# CANnode.net
KiCad netlist of a schematic drawn in EAGLE
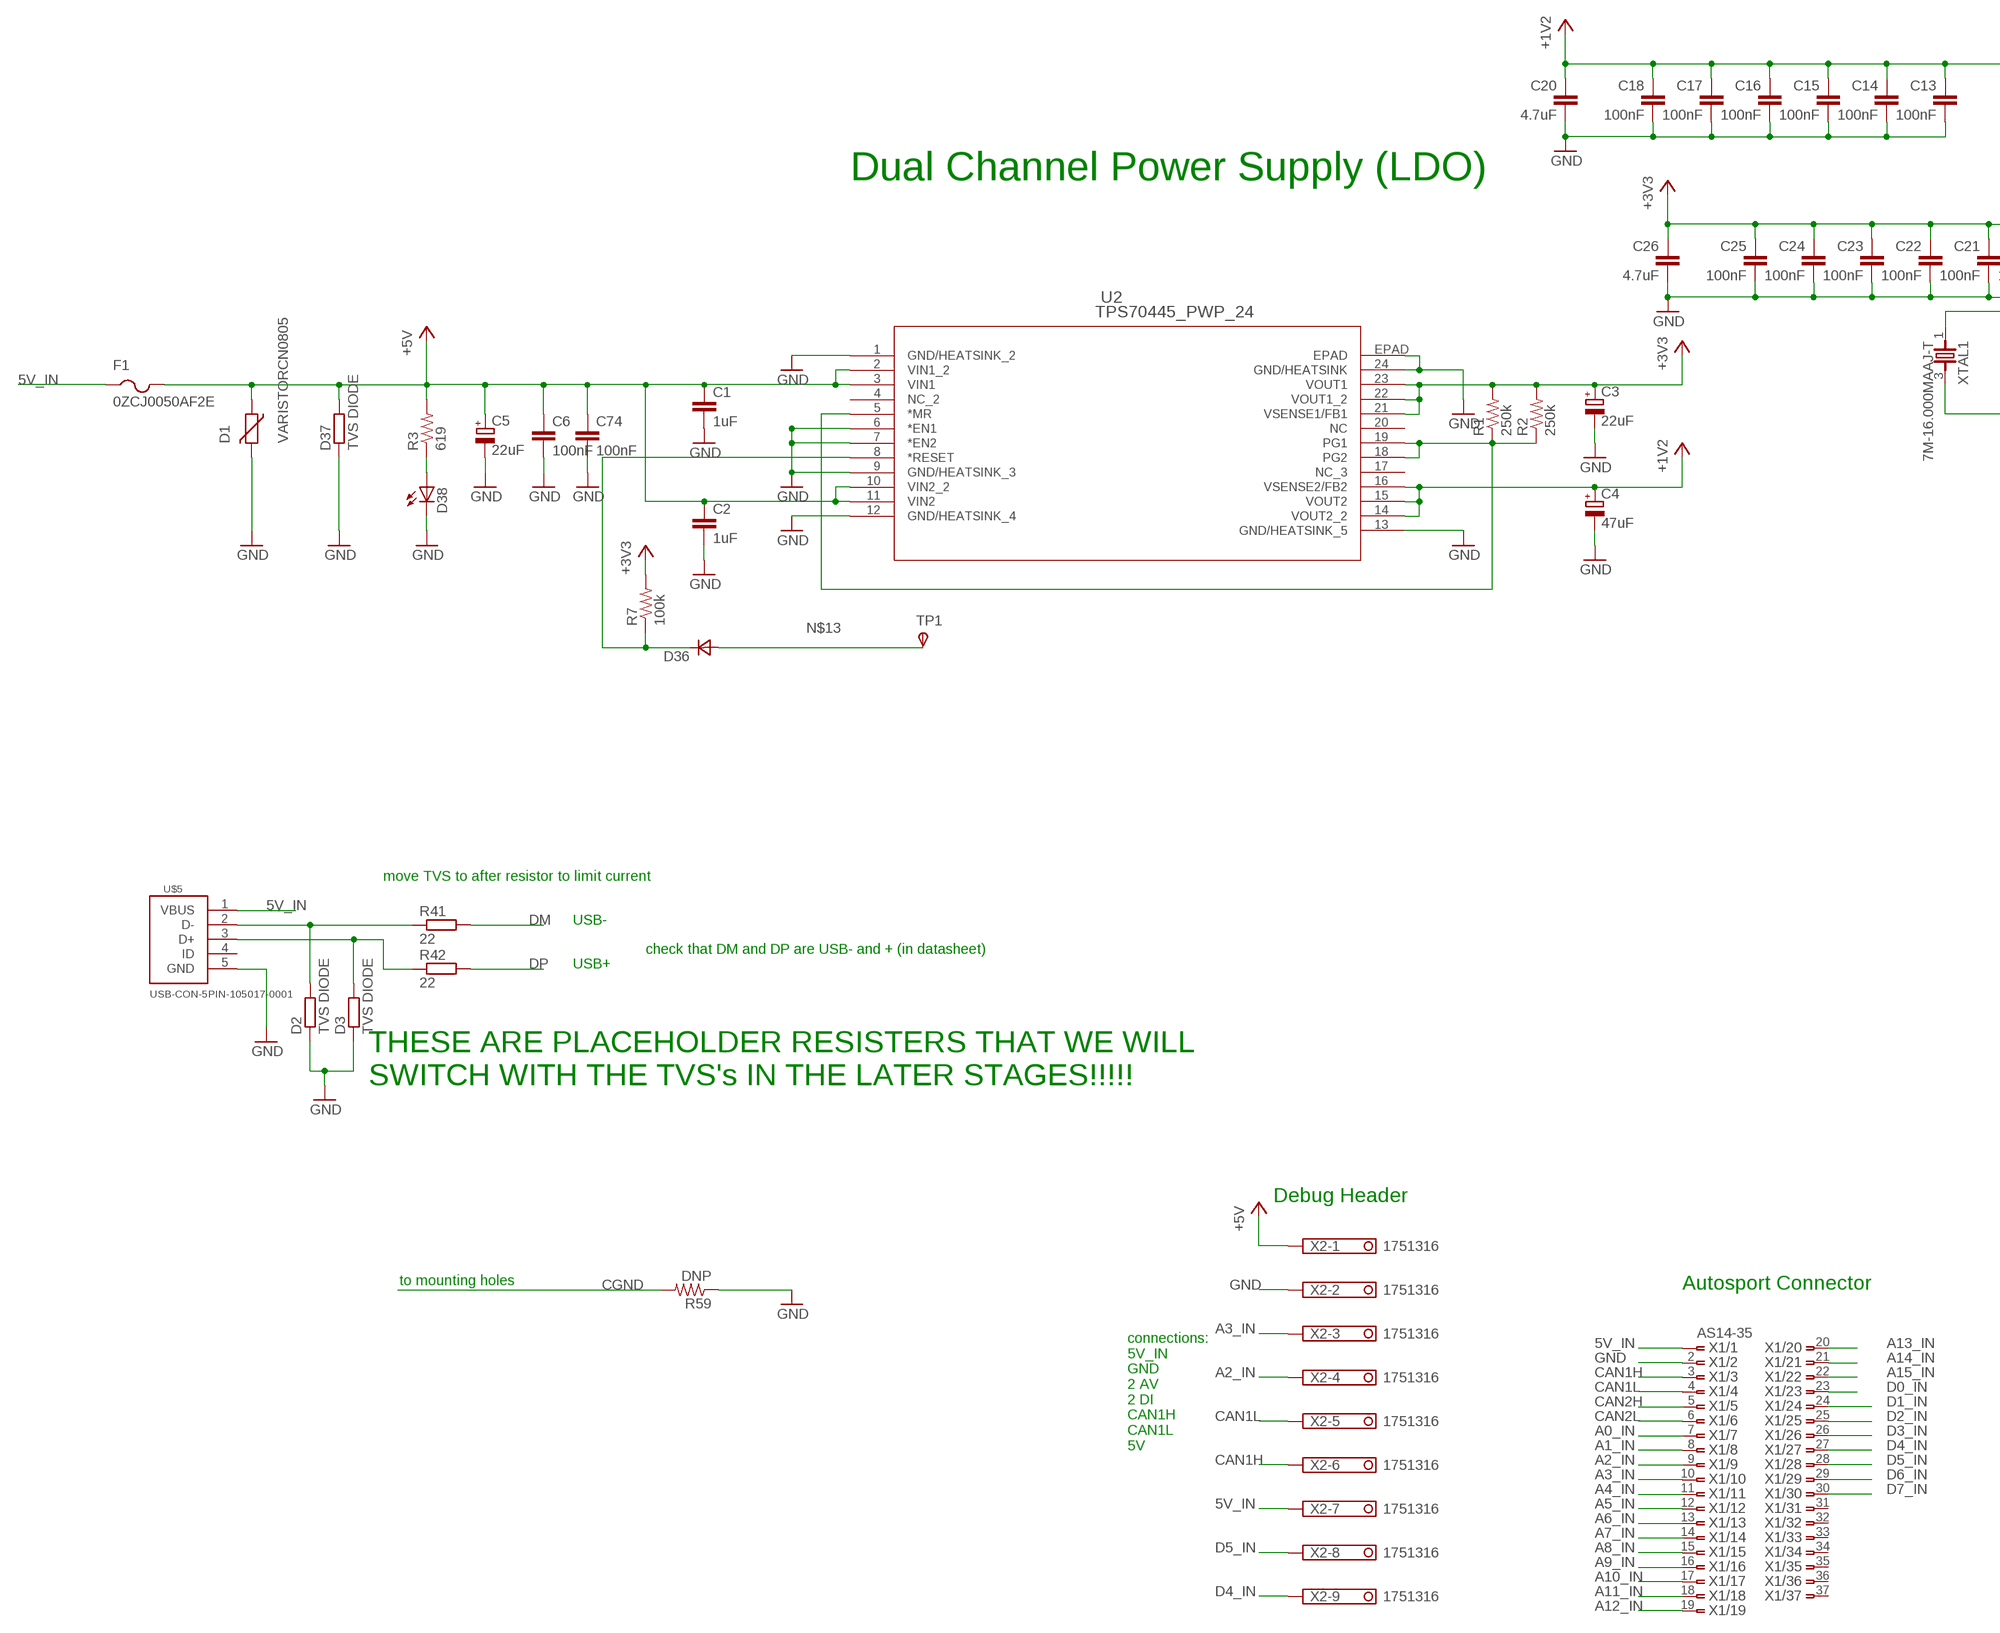
[diagram p0: schematic, sheet 1, part 1 of 3]
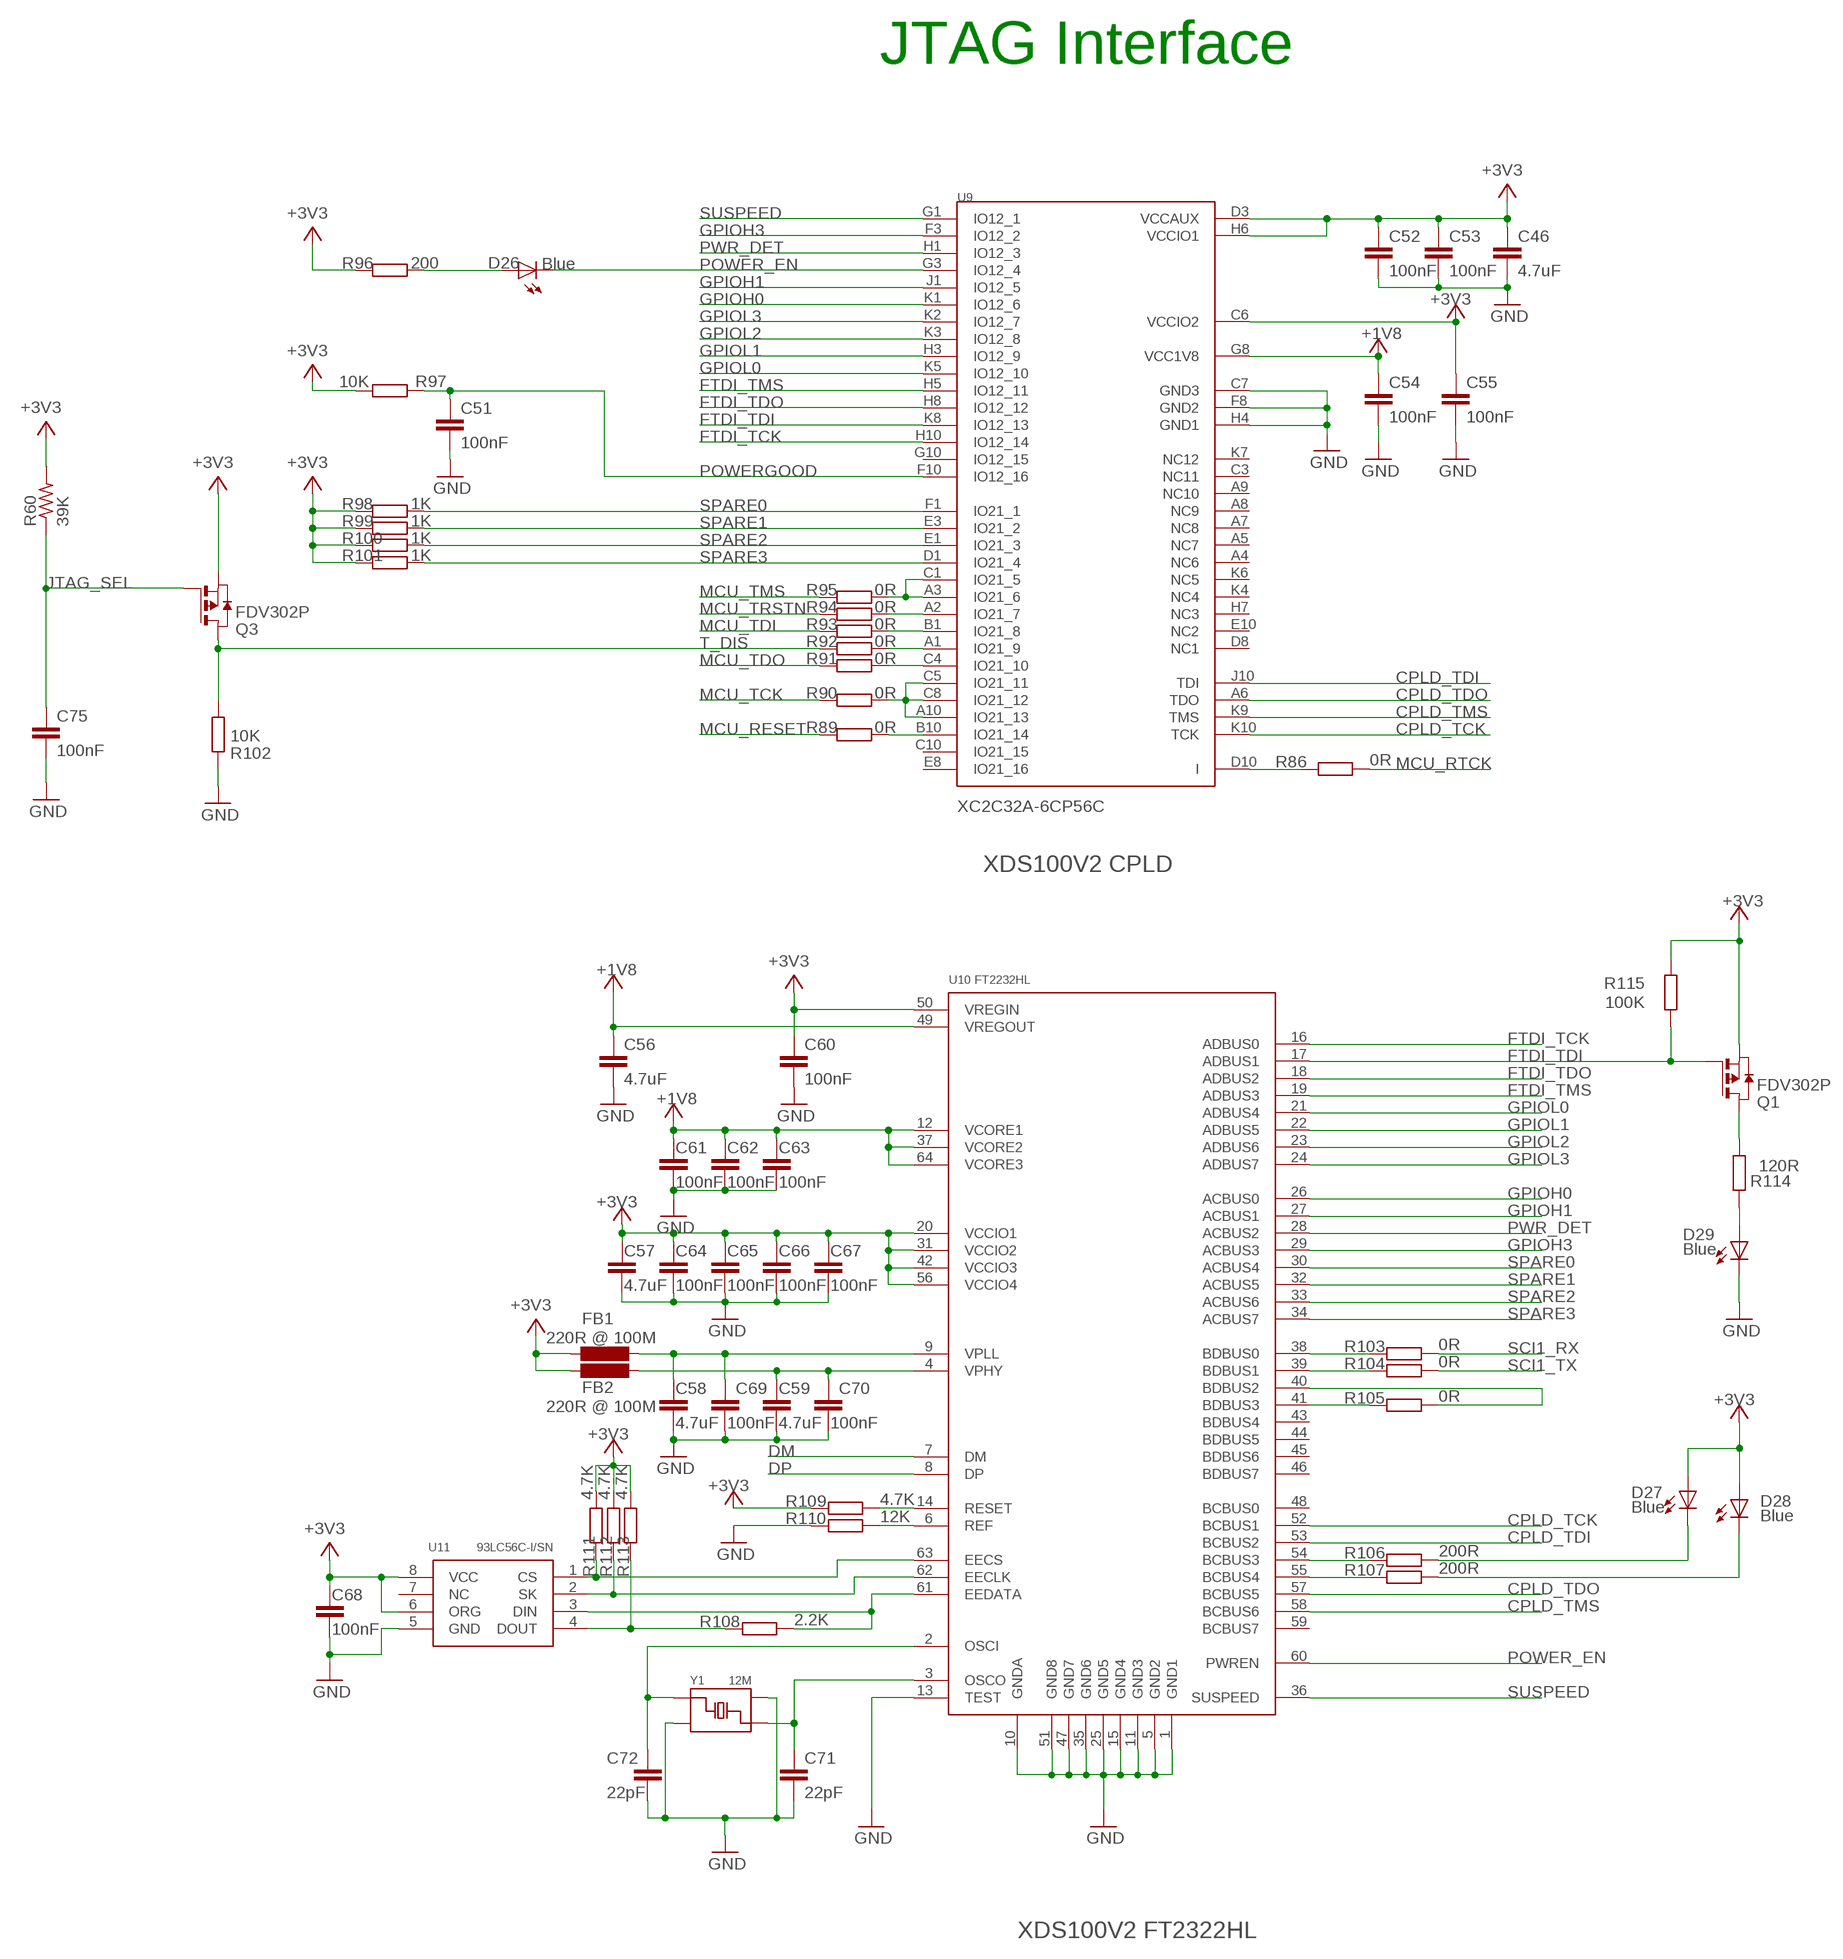
[diagram p1: schematic, sheet 1, part 2 of 3]
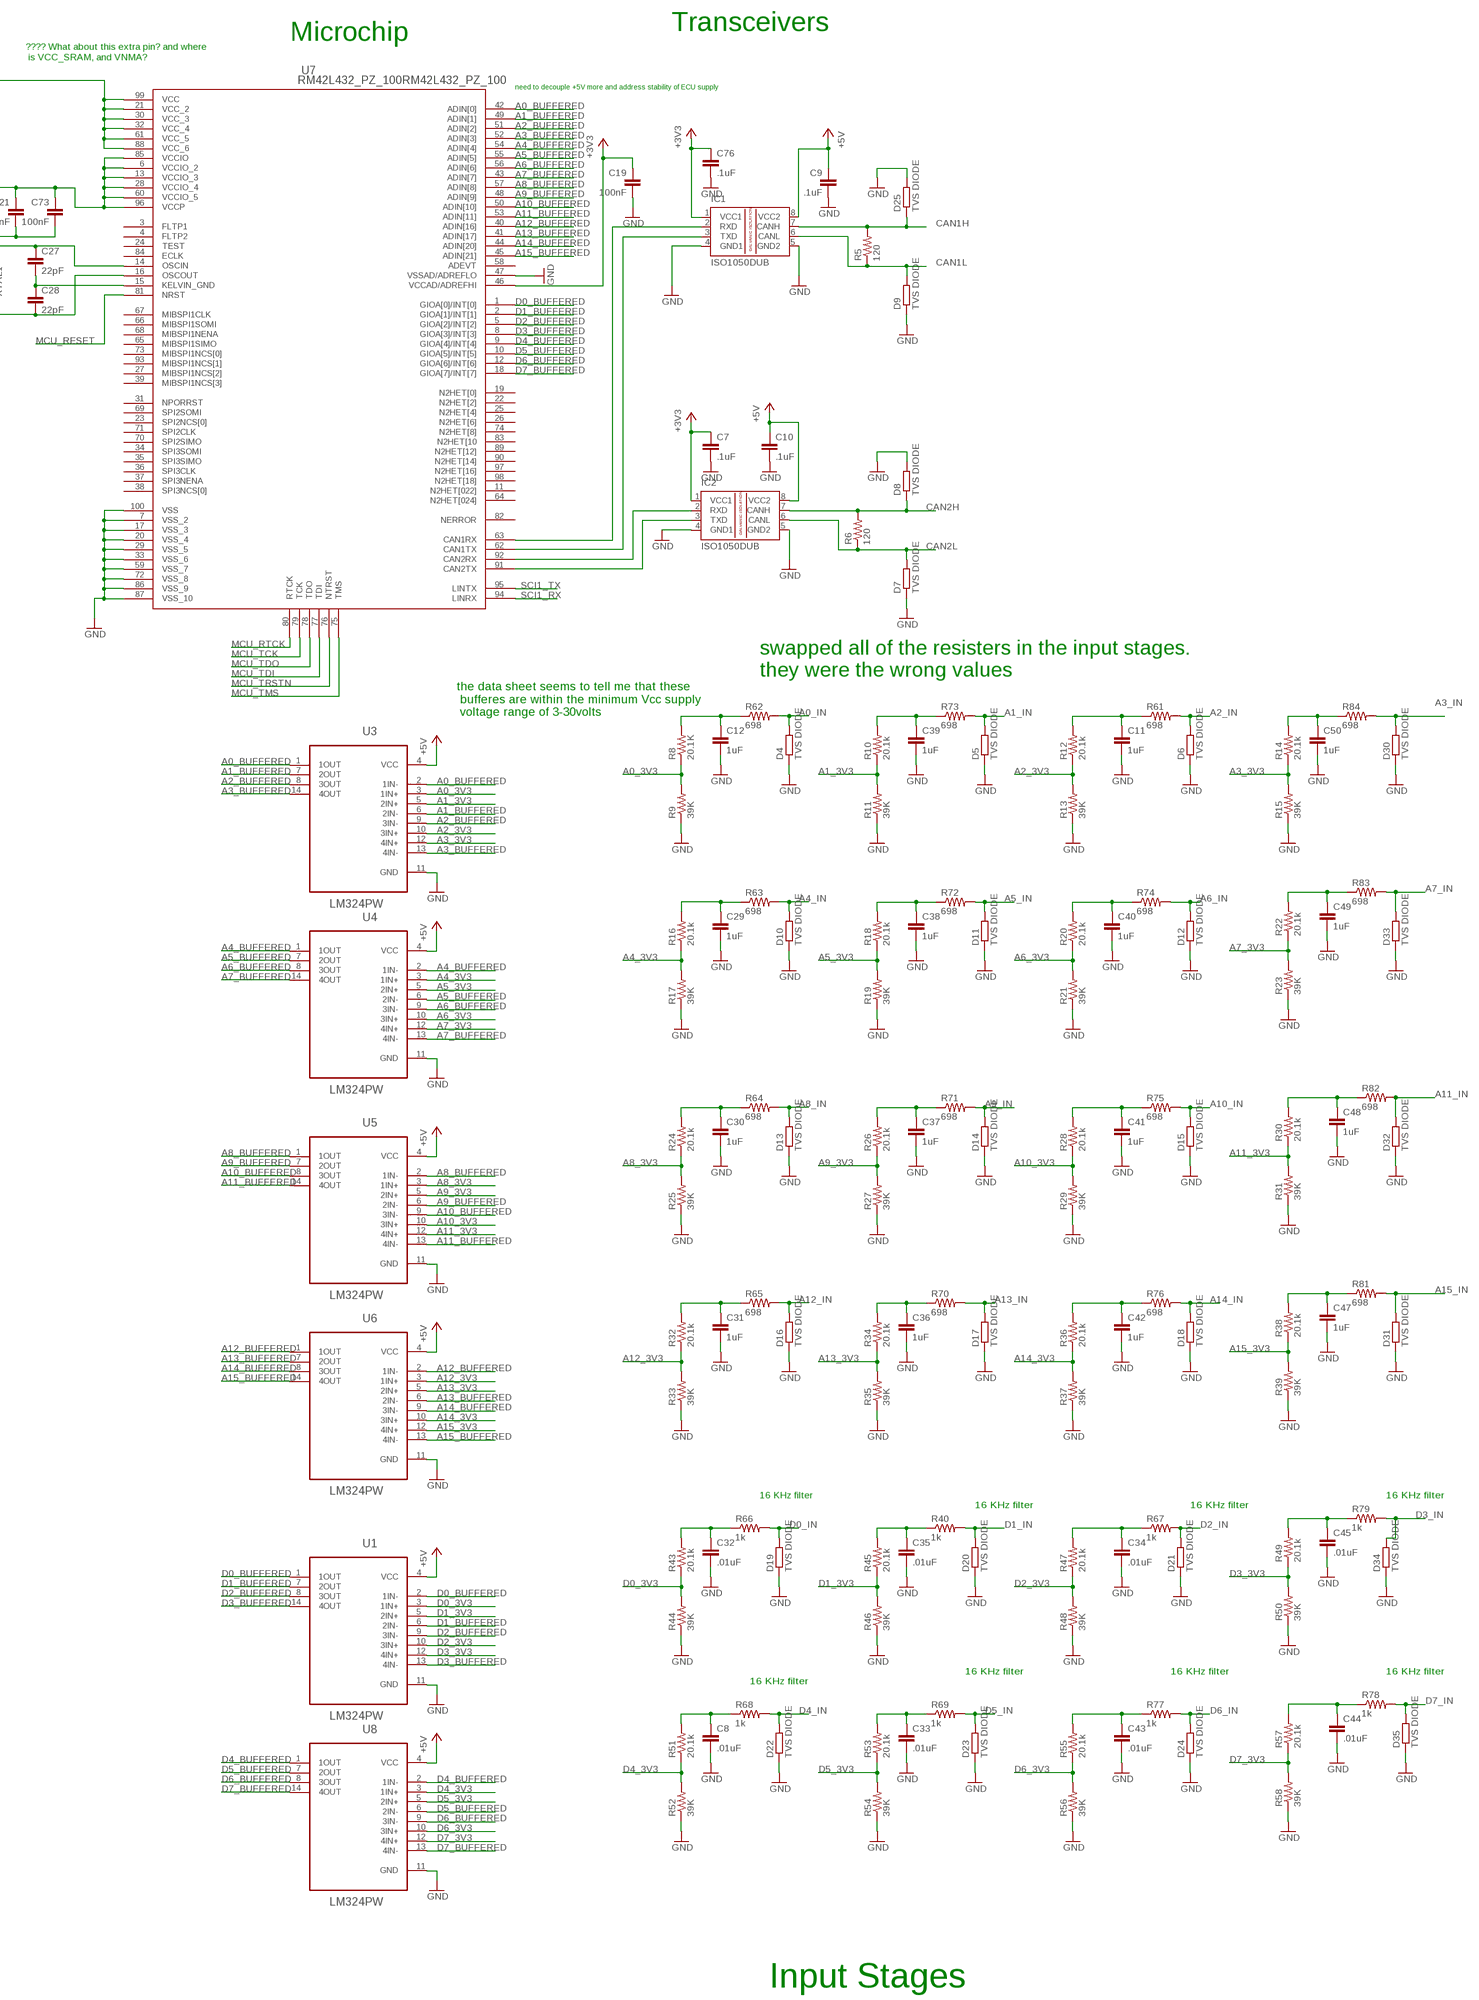
[diagram p2: schematic, sheet 1, part 3 of 3]

(export (version "E")
  (design (tool "Eeschema 10.0.6"))
  (components
    (comp (ref "C1")
      (value "1uF")
      (footprint "eagle-import:C0402")
      (libsource (lib "eagle-import") (part "CC0402"))
    )
    (comp (ref "C2")
      (value "1uF")
      (footprint "eagle-import:C0402")
      (libsource (lib "eagle-import") (part "CC0402"))
    )
    (comp (ref "C3")
      (value "22uF")
      (footprint "eagle-import:CT3528")
      (libsource (lib "eagle-import") (part "CPOL-EUCT3528"))
    )
    (comp (ref "C4")
      (value "47uF")
      (footprint "eagle-import:CT3528")
      (libsource (lib "eagle-import") (part "CPOL-EUCT3528"))
    )
    (comp (ref "C5")
      (value "22uF")
      (footprint "eagle-import:CT3528")
      (libsource (lib "eagle-import") (part "CPOL-EUCT3528"))
    )
    (comp (ref "C6")
      (value "100nF")
      (footprint "eagle-import:C0402")
      (libsource (lib "eagle-import") (part "CC0402"))
    )
    (comp (ref "C7")
      (value ".1uF")
      (footprint "eagle-import:C0402")
      (libsource (lib "eagle-import") (part "C-EUC0402"))
    )
    (comp (ref "C8")
      (value ".01uF")
      (footprint "eagle-import:C0402")
      (libsource (lib "eagle-import") (part "C-EUC0402"))
    )
    (comp (ref "C9")
      (value ".1uF")
      (footprint "eagle-import:C0402")
      (libsource (lib "eagle-import") (part "CC0402"))
    )
    (comp (ref "C10")
      (value ".1uF")
      (footprint "eagle-import:C0402")
      (libsource (lib "eagle-import") (part "CC0402"))
    )
    (comp (ref "C11")
      (value "1uF")
      (footprint "eagle-import:C0402")
      (libsource (lib "eagle-import") (part "C-EUC0402"))
    )
    (comp (ref "C12")
      (value "1uF")
      (footprint "eagle-import:C0402")
      (libsource (lib "eagle-import") (part "C-EUC0402"))
    )
    (comp (ref "C13")
      (value "100nF")
      (footprint "eagle-import:C0402")
      (libsource (lib "eagle-import") (part "C-EUC0402"))
    )
    (comp (ref "C14")
      (value "100nF")
      (footprint "eagle-import:C0402")
      (libsource (lib "eagle-import") (part "C-EUC0402"))
    )
    (comp (ref "C15")
      (value "100nF")
      (footprint "eagle-import:C0402")
      (libsource (lib "eagle-import") (part "C-EUC0402"))
    )
    (comp (ref "C16")
      (value "100nF")
      (footprint "eagle-import:C0402")
      (libsource (lib "eagle-import") (part "C-EUC0402"))
    )
    (comp (ref "C17")
      (value "100nF")
      (footprint "eagle-import:C0402")
      (libsource (lib "eagle-import") (part "C-EUC0402"))
    )
    (comp (ref "C18")
      (value "100nF")
      (footprint "eagle-import:C0402")
      (libsource (lib "eagle-import") (part "C-EUC0402"))
    )
    (comp (ref "C19")
      (value "100nF")
      (footprint "eagle-import:C0402")
      (libsource (lib "eagle-import") (part "C-EUC0402"))
    )
    (comp (ref "C20")
      (value "4.7uF")
      (footprint "eagle-import:C0805")
      (libsource (lib "eagle-import") (part "C-EUC0805"))
    )
    (comp (ref "C21")
      (value "100nF")
      (footprint "eagle-import:C0402")
      (libsource (lib "eagle-import") (part "C-EUC0402"))
    )
    (comp (ref "C22")
      (value "100nF")
      (footprint "eagle-import:C0402")
      (libsource (lib "eagle-import") (part "C-EUC0402"))
    )
    (comp (ref "C23")
      (value "100nF")
      (footprint "eagle-import:C0402")
      (libsource (lib "eagle-import") (part "C-EUC0402"))
    )
    (comp (ref "C24")
      (value "100nF")
      (footprint "eagle-import:C0402")
      (libsource (lib "eagle-import") (part "C-EUC0402"))
    )
    (comp (ref "C25")
      (value "100nF")
      (footprint "eagle-import:C0402")
      (libsource (lib "eagle-import") (part "C-EUC0402"))
    )
    (comp (ref "C26")
      (value "4.7uF")
      (footprint "eagle-import:C0805")
      (libsource (lib "eagle-import") (part "C-EUC0805"))
    )
    (comp (ref "C27")
      (value "22pF")
      (footprint "eagle-import:C0402")
      (libsource (lib "eagle-import") (part "C-EUC0402"))
    )
    (comp (ref "C28")
      (value "22pF")
      (footprint "eagle-import:C0402")
      (libsource (lib "eagle-import") (part "C-EUC0402"))
    )
    (comp (ref "C29")
      (value "1uF")
      (footprint "eagle-import:C0402")
      (libsource (lib "eagle-import") (part "C-EUC0402"))
    )
    (comp (ref "C30")
      (value "1uF")
      (footprint "eagle-import:C0402")
      (libsource (lib "eagle-import") (part "C-EUC0402"))
    )
    (comp (ref "C31")
      (value "1uF")
      (footprint "eagle-import:C0402")
      (libsource (lib "eagle-import") (part "C-EUC0402"))
    )
    (comp (ref "C32")
      (value ".01uF")
      (footprint "eagle-import:C0402")
      (libsource (lib "eagle-import") (part "C-EUC0402"))
    )
    (comp (ref "C33")
      (value ".01uF")
      (footprint "eagle-import:C0402")
      (libsource (lib "eagle-import") (part "C-EUC0402"))
    )
    (comp (ref "C34")
      (value ".01uF")
      (footprint "eagle-import:C0402")
      (libsource (lib "eagle-import") (part "C-EUC0402"))
    )
    (comp (ref "C35")
      (value ".01uF")
      (footprint "eagle-import:C0402")
      (libsource (lib "eagle-import") (part "C-EUC0402"))
    )
    (comp (ref "C36")
      (value "1uF")
      (footprint "eagle-import:C0402")
      (libsource (lib "eagle-import") (part "C-EUC0402"))
    )
    (comp (ref "C37")
      (value "1uF")
      (footprint "eagle-import:C0402")
      (libsource (lib "eagle-import") (part "C-EUC0402"))
    )
    (comp (ref "C38")
      (value "1uF")
      (footprint "eagle-import:C0402")
      (libsource (lib "eagle-import") (part "C-EUC0402"))
    )
    (comp (ref "C39")
      (value "1uF")
      (footprint "eagle-import:C0402")
      (libsource (lib "eagle-import") (part "C-EUC0402"))
    )
    (comp (ref "C40")
      (value "1uF")
      (footprint "eagle-import:C0402")
      (libsource (lib "eagle-import") (part "C-EUC0402"))
    )
    (comp (ref "C41")
      (value "1uF")
      (footprint "eagle-import:C0402")
      (libsource (lib "eagle-import") (part "C-EUC0402"))
    )
    (comp (ref "C42")
      (value "1uF")
      (footprint "eagle-import:C0402")
      (libsource (lib "eagle-import") (part "C-EUC0402"))
    )
    (comp (ref "C43")
      (value ".01uF")
      (footprint "eagle-import:C0402")
      (libsource (lib "eagle-import") (part "C-EUC0402"))
    )
    (comp (ref "C44")
      (value ".01uF")
      (footprint "eagle-import:C0402")
      (libsource (lib "eagle-import") (part "C-EUC0402"))
    )
    (comp (ref "C45")
      (value ".01uF")
      (footprint "eagle-import:C0402")
      (libsource (lib "eagle-import") (part "C-EUC0402"))
    )
    (comp (ref "C46")
      (value "4.7uF")
      (footprint "eagle-import:0805")
      (libsource (lib "eagle-import") (part "CAP0805"))
    )
    (comp (ref "C47")
      (value "1uF")
      (footprint "eagle-import:C0402")
      (libsource (lib "eagle-import") (part "C-EUC0402"))
    )
    (comp (ref "C48")
      (value "1uF")
      (footprint "eagle-import:C0402")
      (libsource (lib "eagle-import") (part "C-EUC0402"))
    )
    (comp (ref "C49")
      (value "1uF")
      (footprint "eagle-import:C0402")
      (libsource (lib "eagle-import") (part "C-EUC0402"))
    )
    (comp (ref "C50")
      (value "1uF")
      (footprint "eagle-import:C0402")
      (libsource (lib "eagle-import") (part "C-EUC0402"))
    )
    (comp (ref "C51")
      (value "100nF")
      (footprint "eagle-import:0402")
      (libsource (lib "eagle-import") (part "CAP0402"))
    )
    (comp (ref "C52")
      (value "100nF")
      (footprint "eagle-import:0402")
      (libsource (lib "eagle-import") (part "CAP0402"))
    )
    (comp (ref "C53")
      (value "100nF")
      (footprint "eagle-import:0402")
      (libsource (lib "eagle-import") (part "CAP0402"))
    )
    (comp (ref "C54")
      (value "100nF")
      (footprint "eagle-import:0402")
      (libsource (lib "eagle-import") (part "CAP0402"))
    )
    (comp (ref "C55")
      (value "100nF")
      (footprint "eagle-import:0402")
      (libsource (lib "eagle-import") (part "CAP0402"))
    )
    (comp (ref "C56")
      (value "4.7uF")
      (footprint "eagle-import:0805")
      (libsource (lib "eagle-import") (part "CAP0805"))
    )
    (comp (ref "C57")
      (value "4.7uF")
      (footprint "eagle-import:0805")
      (libsource (lib "eagle-import") (part "CAP0805"))
    )
    (comp (ref "C58")
      (value "4.7uF")
      (footprint "eagle-import:0805")
      (libsource (lib "eagle-import") (part "CAP0805"))
    )
    (comp (ref "C59")
      (value "4.7uF")
      (footprint "eagle-import:0805")
      (libsource (lib "eagle-import") (part "CAP0805"))
    )
    (comp (ref "C60")
      (value "100nF")
      (footprint "eagle-import:0402")
      (libsource (lib "eagle-import") (part "CAP0402"))
    )
    (comp (ref "C61")
      (value "100nF")
      (footprint "eagle-import:0402")
      (libsource (lib "eagle-import") (part "CAP0402"))
    )
    (comp (ref "C62")
      (value "100nF")
      (footprint "eagle-import:0402")
      (libsource (lib "eagle-import") (part "CAP0402"))
    )
    (comp (ref "C63")
      (value "100nF")
      (footprint "eagle-import:0402")
      (libsource (lib "eagle-import") (part "CAP0402"))
    )
    (comp (ref "C64")
      (value "100nF")
      (footprint "eagle-import:0402")
      (libsource (lib "eagle-import") (part "CAP0402"))
    )
    (comp (ref "C65")
      (value "100nF")
      (footprint "eagle-import:0402")
      (libsource (lib "eagle-import") (part "CAP0402"))
    )
    (comp (ref "C66")
      (value "100nF")
      (footprint "eagle-import:0402")
      (libsource (lib "eagle-import") (part "CAP0402"))
    )
    (comp (ref "C67")
      (value "100nF")
      (footprint "eagle-import:0402")
      (libsource (lib "eagle-import") (part "CAP0402"))
    )
    (comp (ref "C68")
      (value "100nF")
      (footprint "eagle-import:0402")
      (libsource (lib "eagle-import") (part "CAP0402"))
    )
    (comp (ref "C69")
      (value "100nF")
      (footprint "eagle-import:0402")
      (libsource (lib "eagle-import") (part "CAP0402"))
    )
    (comp (ref "C70")
      (value "100nF")
      (footprint "eagle-import:0402")
      (libsource (lib "eagle-import") (part "CAP0402"))
    )
    (comp (ref "C71")
      (value "22pF")
      (footprint "eagle-import:0402")
      (libsource (lib "eagle-import") (part "CAP0402"))
    )
    (comp (ref "C72")
      (value "22pF")
      (footprint "eagle-import:0402")
      (libsource (lib "eagle-import") (part "CAP0402"))
    )
    (comp (ref "C73")
      (value "100nF")
      (footprint "eagle-import:C0402")
      (libsource (lib "eagle-import") (part "C-EUC0402"))
    )
    (comp (ref "C74")
      (value "100nF")
      (footprint "eagle-import:C0402")
      (libsource (lib "eagle-import") (part "CC0402"))
    )
    (comp (ref "C75")
      (value "100nF")
      (footprint "eagle-import:C0402")
      (libsource (lib "eagle-import") (part "C-EUC0402"))
    )
    (comp (ref "C76")
      (value ".1uF")
      (footprint "eagle-import:C0402")
      (libsource (lib "eagle-import") (part "C-EUC0402"))
    )
    (comp (ref "D1")
      (value "VARISTORCN0805")
      (footprint "eagle-import:CT_CN0805")
      (libsource (lib "eagle-import") (part "VARISTORCN0805"))
    )
    (comp (ref "D2")
      (value "TVS DIODE")
      (footprint "eagle-import:R0402")
      (libsource (lib "eagle-import") (part "RR0402"))
    )
    (comp (ref "D3")
      (value "TVS DIODE")
      (footprint "eagle-import:R0402")
      (libsource (lib "eagle-import") (part "RR0402"))
    )
    (comp (ref "D4")
      (value "TVS DIODE")
      (footprint "eagle-import:R0402")
      (libsource (lib "eagle-import") (part "RR0402"))
    )
    (comp (ref "D5")
      (value "TVS DIODE")
      (footprint "eagle-import:R0402")
      (libsource (lib "eagle-import") (part "RR0402"))
    )
    (comp (ref "D6")
      (value "TVS DIODE")
      (footprint "eagle-import:R0402")
      (libsource (lib "eagle-import") (part "RR0402"))
    )
    (comp (ref "D7")
      (value "TVS DIODE")
      (footprint "eagle-import:R0402")
      (libsource (lib "eagle-import") (part "RR0402"))
    )
    (comp (ref "D8")
      (value "TVS DIODE")
      (footprint "eagle-import:R0402")
      (libsource (lib "eagle-import") (part "RR0402"))
    )
    (comp (ref "D9")
      (value "TVS DIODE")
      (footprint "eagle-import:R0402")
      (libsource (lib "eagle-import") (part "RR0402"))
    )
    (comp (ref "D10")
      (value "TVS DIODE")
      (footprint "eagle-import:R0402")
      (libsource (lib "eagle-import") (part "RR0402"))
    )
    (comp (ref "D11")
      (value "TVS DIODE")
      (footprint "eagle-import:R0402")
      (libsource (lib "eagle-import") (part "RR0402"))
    )
    (comp (ref "D12")
      (value "TVS DIODE")
      (footprint "eagle-import:R0402")
      (libsource (lib "eagle-import") (part "RR0402"))
    )
    (comp (ref "D13")
      (value "TVS DIODE")
      (footprint "eagle-import:R0402")
      (libsource (lib "eagle-import") (part "RR0402"))
    )
    (comp (ref "D14")
      (value "TVS DIODE")
      (footprint "eagle-import:R0402")
      (libsource (lib "eagle-import") (part "RR0402"))
    )
    (comp (ref "D15")
      (value "TVS DIODE")
      (footprint "eagle-import:R0402")
      (libsource (lib "eagle-import") (part "RR0402"))
    )
    (comp (ref "D16")
      (value "TVS DIODE")
      (footprint "eagle-import:R0402")
      (libsource (lib "eagle-import") (part "RR0402"))
    )
    (comp (ref "D17")
      (value "TVS DIODE")
      (footprint "eagle-import:R0402")
      (libsource (lib "eagle-import") (part "RR0402"))
    )
    (comp (ref "D18")
      (value "TVS DIODE")
      (footprint "eagle-import:R0402")
      (libsource (lib "eagle-import") (part "RR0402"))
    )
    (comp (ref "D19")
      (value "TVS DIODE")
      (footprint "eagle-import:R0402")
      (libsource (lib "eagle-import") (part "RR0402"))
    )
    (comp (ref "D20")
      (value "TVS DIODE")
      (footprint "eagle-import:R0402")
      (libsource (lib "eagle-import") (part "RR0402"))
    )
    (comp (ref "D21")
      (value "TVS DIODE")
      (footprint "eagle-import:R0402")
      (libsource (lib "eagle-import") (part "RR0402"))
    )
    (comp (ref "D22")
      (value "TVS DIODE")
      (footprint "eagle-import:R0402")
      (libsource (lib "eagle-import") (part "RR0402"))
    )
    (comp (ref "D23")
      (value "TVS DIODE")
      (footprint "eagle-import:R0402")
      (libsource (lib "eagle-import") (part "RR0402"))
    )
    (comp (ref "D24")
      (value "TVS DIODE")
      (footprint "eagle-import:R0402")
      (libsource (lib "eagle-import") (part "RR0402"))
    )
    (comp (ref "D25")
      (value "TVS DIODE")
      (footprint "eagle-import:R0402")
      (libsource (lib "eagle-import") (part "RR0402"))
    )
    (comp (ref "D26")
      (value "Blue")
      (footprint "eagle-import:LED0805")
      (libsource (lib "eagle-import") (part "CHIP-LED"))
    )
    (comp (ref "D27")
      (value "Blue")
      (footprint "eagle-import:LED0805")
      (libsource (lib "eagle-import") (part "CHIP-LED"))
    )
    (comp (ref "D28")
      (value "Blue")
      (footprint "eagle-import:LED0805")
      (libsource (lib "eagle-import") (part "CHIP-LED"))
    )
    (comp (ref "D29")
      (value "Blue")
      (footprint "eagle-import:LED0805")
      (libsource (lib "eagle-import") (part "CHIP-LED"))
    )
    (comp (ref "D30")
      (value "TVS DIODE")
      (footprint "eagle-import:R0402")
      (libsource (lib "eagle-import") (part "RR0402"))
    )
    (comp (ref "D31")
      (value "TVS DIODE")
      (footprint "eagle-import:R0402")
      (libsource (lib "eagle-import") (part "RR0402"))
    )
    (comp (ref "D32")
      (value "TVS DIODE")
      (footprint "eagle-import:R0402")
      (libsource (lib "eagle-import") (part "RR0402"))
    )
    (comp (ref "D33")
      (value "TVS DIODE")
      (footprint "eagle-import:R0402")
      (libsource (lib "eagle-import") (part "RR0402"))
    )
    (comp (ref "D34")
      (value "TVS DIODE")
      (footprint "eagle-import:R0402")
      (libsource (lib "eagle-import") (part "RR0402"))
    )
    (comp (ref "D35")
      (value "TVS DIODE")
      (footprint "eagle-import:R0402")
      (libsource (lib "eagle-import") (part "RR0402"))
    )
    (comp (ref "D36")
      (value "DSOD323")
      (footprint "eagle-import:SOD323")
      (fields (field (name "MPN") "CDSOD323-T05C"))
      (libsource (lib "eagle-import") (part "DSOD323"))
    )
    (comp (ref "D37")
      (value "TVS DIODE")
      (footprint "eagle-import:R0402")
      (libsource (lib "eagle-import") (part "RR0402"))
    )
    (comp (ref "D38")
      (value "LED")
      (footprint "eagle-import:SMARTLED-TTW")
      (libsource (lib "eagle-import") (part "LED"))
    )
    (comp (ref "F1")
      (value "0ZCJ0050AF2E")
      (footprint "eagle-import:R1206")
      (libsource (lib "eagle-import") (part "PTCFUSE-1206"))
    )
    (comp (ref "FB1")
      (value "220R @ 100M")
      (footprint "eagle-import:0805")
      (libsource (lib "eagle-import") (part "INDUCTOR"))
    )
    (comp (ref "FB2")
      (value "220R @ 100M")
      (footprint "eagle-import:0805")
      (libsource (lib "eagle-import") (part "INDUCTOR"))
    )
    (comp (ref "IC1")
      (value "ISO1050DUB")
      (footprint "eagle-import:DUB-R-PDSO-G8")
      (fields (field (name "MPN") "ISO1050DUBR"))
      (libsource (lib "eagle-import") (part "ISO1050DUB"))
    )
    (comp (ref "IC2")
      (value "ISO1050DUB")
      (footprint "eagle-import:DUB-R-PDSO-G8")
      (fields (field (name "MPN") "ISO1050DUBR"))
      (libsource (lib "eagle-import") (part "ISO1050DUB"))
    )
    (comp (ref "Q1")
      (value "FDV302P")
      (footprint "eagle-import:SOT-23")
      (libsource (lib "eagle-import") (part "PMOSSOT23"))
    )
    (comp (ref "Q3")
      (value "FDV302P")
      (footprint "eagle-import:SOT-23")
      (libsource (lib "eagle-import") (part "PMOSSOT23"))
    )
    (comp (ref "R1")
      (value "250k")
      (footprint "eagle-import:R0402")
      (libsource (lib "eagle-import") (part "resistor_R-US_R0402"))
    )
    (comp (ref "R2")
      (value "250k")
      (footprint "eagle-import:R0402")
      (libsource (lib "eagle-import") (part "resistor_R-US_R0402"))
    )
    (comp (ref "R3")
      (value "619")
      (footprint "eagle-import:R0402")
      (libsource (lib "eagle-import") (part "resistor_R-US_R0402"))
    )
    (comp (ref "R5")
      (value "120")
      (footprint "eagle-import:R0402")
      (libsource (lib "eagle-import") (part "resistor_R-US_R0402"))
    )
    (comp (ref "R6")
      (value "120")
      (footprint "eagle-import:R0402")
      (libsource (lib "eagle-import") (part "resistor_R-US_R0402"))
    )
    (comp (ref "R7")
      (value "100k")
      (footprint "eagle-import:R0402")
      (libsource (lib "eagle-import") (part "resistor_R-US_R0402"))
    )
    (comp (ref "R8")
      (value "20.1K")
      (footprint "eagle-import:R0402")
      (libsource (lib "eagle-import") (part "resistor_R-US_R0402"))
    )
    (comp (ref "R9")
      (value "39K")
      (footprint "eagle-import:R0402")
      (libsource (lib "eagle-import") (part "resistor_R-US_R0402"))
    )
    (comp (ref "R10")
      (value "20.1k")
      (footprint "eagle-import:R0402")
      (libsource (lib "eagle-import") (part "resistor_R-US_R0402"))
    )
    (comp (ref "R11")
      (value "39K")
      (footprint "eagle-import:R0402")
      (libsource (lib "eagle-import") (part "resistor_R-US_R0402"))
    )
    (comp (ref "R12")
      (value "20.1k")
      (footprint "eagle-import:R0402")
      (libsource (lib "eagle-import") (part "resistor_R-US_R0402"))
    )
    (comp (ref "R13")
      (value "39K")
      (footprint "eagle-import:R0402")
      (libsource (lib "eagle-import") (part "resistor_R-US_R0402"))
    )
    (comp (ref "R14")
      (value "20.1k")
      (footprint "eagle-import:R0402")
      (libsource (lib "eagle-import") (part "resistor_R-US_R0402"))
    )
    (comp (ref "R15")
      (value "39K")
      (footprint "eagle-import:R0402")
      (libsource (lib "eagle-import") (part "resistor_R-US_R0402"))
    )
    (comp (ref "R16")
      (value "20.1k")
      (footprint "eagle-import:R0402")
      (libsource (lib "eagle-import") (part "resistor_R-US_R0402"))
    )
    (comp (ref "R17")
      (value "39K")
      (footprint "eagle-import:R0402")
      (libsource (lib "eagle-import") (part "resistor_R-US_R0402"))
    )
    (comp (ref "R18")
      (value "20.1k")
      (footprint "eagle-import:R0402")
      (libsource (lib "eagle-import") (part "resistor_R-US_R0402"))
    )
    (comp (ref "R19")
      (value "39K")
      (footprint "eagle-import:R0402")
      (libsource (lib "eagle-import") (part "resistor_R-US_R0402"))
    )
    (comp (ref "R20")
      (value "20.1k")
      (footprint "eagle-import:R0402")
      (libsource (lib "eagle-import") (part "resistor_R-US_R0402"))
    )
    (comp (ref "R21")
      (value "39K")
      (footprint "eagle-import:R0402")
      (libsource (lib "eagle-import") (part "resistor_R-US_R0402"))
    )
    (comp (ref "R22")
      (value "20.1k")
      (footprint "eagle-import:R0402")
      (libsource (lib "eagle-import") (part "resistor_R-US_R0402"))
    )
    (comp (ref "R23")
      (value "39K")
      (footprint "eagle-import:R0402")
      (libsource (lib "eagle-import") (part "resistor_R-US_R0402"))
    )
    (comp (ref "R24")
      (value "20.1k")
      (footprint "eagle-import:R0402")
      (libsource (lib "eagle-import") (part "resistor_R-US_R0402"))
    )
    (comp (ref "R25")
      (value "39K")
      (footprint "eagle-import:R0402")
      (libsource (lib "eagle-import") (part "resistor_R-US_R0402"))
    )
    (comp (ref "R26")
      (value "20.1k")
      (footprint "eagle-import:R0402")
      (libsource (lib "eagle-import") (part "resistor_R-US_R0402"))
    )
    (comp (ref "R27")
      (value "39K")
      (footprint "eagle-import:R0402")
      (libsource (lib "eagle-import") (part "resistor_R-US_R0402"))
    )
    (comp (ref "R28")
      (value "20.1k")
      (footprint "eagle-import:R0402")
      (libsource (lib "eagle-import") (part "resistor_R-US_R0402"))
    )
    (comp (ref "R29")
      (value "39K")
      (footprint "eagle-import:R0402")
      (libsource (lib "eagle-import") (part "resistor_R-US_R0402"))
    )
    (comp (ref "R30")
      (value "20.1k")
      (footprint "eagle-import:R0402")
      (libsource (lib "eagle-import") (part "resistor_R-US_R0402"))
    )
    (comp (ref "R31")
      (value "39K")
      (footprint "eagle-import:R0402")
      (libsource (lib "eagle-import") (part "resistor_R-US_R0402"))
    )
    (comp (ref "R32")
      (value "20.1k")
      (footprint "eagle-import:R0402")
      (libsource (lib "eagle-import") (part "resistor_R-US_R0402"))
    )
    (comp (ref "R33")
      (value "39K")
      (footprint "eagle-import:R0402")
      (libsource (lib "eagle-import") (part "resistor_R-US_R0402"))
    )
    (comp (ref "R34")
      (value "20.1k")
      (footprint "eagle-import:R0402")
      (libsource (lib "eagle-import") (part "resistor_R-US_R0402"))
    )
    (comp (ref "R35")
      (value "39K")
      (footprint "eagle-import:R0402")
      (libsource (lib "eagle-import") (part "resistor_R-US_R0402"))
    )
    (comp (ref "R36")
      (value "20.1k")
      (footprint "eagle-import:R0402")
      (libsource (lib "eagle-import") (part "resistor_R-US_R0402"))
    )
    (comp (ref "R37")
      (value "39K")
      (footprint "eagle-import:R0402")
      (libsource (lib "eagle-import") (part "resistor_R-US_R0402"))
    )
    (comp (ref "R38")
      (value "20.1k")
      (footprint "eagle-import:R0402")
      (libsource (lib "eagle-import") (part "resistor_R-US_R0402"))
    )
    (comp (ref "R39")
      (value "39K")
      (footprint "eagle-import:R0402")
      (libsource (lib "eagle-import") (part "resistor_R-US_R0402"))
    )
    (comp (ref "R40")
      (value "1k")
      (footprint "eagle-import:R0402")
      (libsource (lib "eagle-import") (part "R-US_R0402"))
    )
    (comp (ref "R41")
      (value "22")
      (footprint "eagle-import:R0402")
      (libsource (lib "eagle-import") (part "RR0402"))
    )
    (comp (ref "R42")
      (value "22")
      (footprint "eagle-import:R0402")
      (libsource (lib "eagle-import") (part "RR0402"))
    )
    (comp (ref "R43")
      (value "20.1k")
      (footprint "eagle-import:R0402")
      (libsource (lib "eagle-import") (part "resistor_R-US_R0402"))
    )
    (comp (ref "R44")
      (value "39K")
      (footprint "eagle-import:R0402")
      (libsource (lib "eagle-import") (part "resistor_R-US_R0402"))
    )
    (comp (ref "R45")
      (value "20.1k")
      (footprint "eagle-import:R0402")
      (libsource (lib "eagle-import") (part "resistor_R-US_R0402"))
    )
    (comp (ref "R46")
      (value "39K")
      (footprint "eagle-import:R0402")
      (libsource (lib "eagle-import") (part "resistor_R-US_R0402"))
    )
    (comp (ref "R47")
      (value "20.1k")
      (footprint "eagle-import:R0402")
      (libsource (lib "eagle-import") (part "resistor_R-US_R0402"))
    )
    (comp (ref "R48")
      (value "39K")
      (footprint "eagle-import:R0402")
      (libsource (lib "eagle-import") (part "resistor_R-US_R0402"))
    )
    (comp (ref "R49")
      (value "20.1k")
      (footprint "eagle-import:R0402")
      (libsource (lib "eagle-import") (part "resistor_R-US_R0402"))
    )
    (comp (ref "R50")
      (value "39K")
      (footprint "eagle-import:R0402")
      (libsource (lib "eagle-import") (part "resistor_R-US_R0402"))
    )
    (comp (ref "R51")
      (value "20.1k")
      (footprint "eagle-import:R0402")
      (libsource (lib "eagle-import") (part "resistor_R-US_R0402"))
    )
    (comp (ref "R52")
      (value "39K")
      (footprint "eagle-import:R0402")
      (libsource (lib "eagle-import") (part "resistor_R-US_R0402"))
    )
    (comp (ref "R53")
      (value "20.1k")
      (footprint "eagle-import:R0402")
      (libsource (lib "eagle-import") (part "resistor_R-US_R0402"))
    )
    (comp (ref "R54")
      (value "39K")
      (footprint "eagle-import:R0402")
      (libsource (lib "eagle-import") (part "resistor_R-US_R0402"))
    )
    (comp (ref "R55")
      (value "20.1k")
      (footprint "eagle-import:R0402")
      (libsource (lib "eagle-import") (part "resistor_R-US_R0402"))
    )
    (comp (ref "R56")
      (value "39K")
      (footprint "eagle-import:R0402")
      (libsource (lib "eagle-import") (part "resistor_R-US_R0402"))
    )
    (comp (ref "R57")
      (value "20.1k")
      (footprint "eagle-import:R0402")
      (libsource (lib "eagle-import") (part "resistor_R-US_R0402"))
    )
    (comp (ref "R58")
      (value "39K")
      (footprint "eagle-import:R0402")
      (libsource (lib "eagle-import") (part "resistor_R-US_R0402"))
    )
    (comp (ref "R59")
      (value "DNP")
      (footprint "eagle-import:R0402")
      (libsource (lib "eagle-import") (part "resistor_R-US_R0402"))
    )
    (comp (ref "R60")
      (value "39K")
      (footprint "eagle-import:R0402")
      (libsource (lib "eagle-import") (part "resistor_R-US_R0402"))
    )
    (comp (ref "R61")
      (value "698")
      (footprint "eagle-import:R0402")
      (libsource (lib "eagle-import") (part "R-US_R0402"))
    )
    (comp (ref "R62")
      (value "698")
      (footprint "eagle-import:R0402")
      (libsource (lib "eagle-import") (part "R-US_R0402"))
    )
    (comp (ref "R63")
      (value "698")
      (footprint "eagle-import:R0402")
      (libsource (lib "eagle-import") (part "R-US_R0402"))
    )
    (comp (ref "R64")
      (value "698")
      (footprint "eagle-import:R0402")
      (libsource (lib "eagle-import") (part "R-US_R0402"))
    )
    (comp (ref "R65")
      (value "698")
      (footprint "eagle-import:R0402")
      (libsource (lib "eagle-import") (part "R-US_R0402"))
    )
    (comp (ref "R66")
      (value "1k")
      (footprint "eagle-import:R0402")
      (libsource (lib "eagle-import") (part "R-US_R0402"))
    )
    (comp (ref "R67")
      (value "1k")
      (footprint "eagle-import:R0402")
      (libsource (lib "eagle-import") (part "R-US_R0402"))
    )
    (comp (ref "R68")
      (value "1k")
      (footprint "eagle-import:R0402")
      (libsource (lib "eagle-import") (part "R-US_R0402"))
    )
    (comp (ref "R69")
      (value "1k")
      (footprint "eagle-import:R0402")
      (libsource (lib "eagle-import") (part "R-US_R0402"))
    )
    (comp (ref "R70")
      (value "698")
      (footprint "eagle-import:R0402")
      (libsource (lib "eagle-import") (part "R-US_R0402"))
    )
    (comp (ref "R71")
      (value "698")
      (footprint "eagle-import:R0402")
      (libsource (lib "eagle-import") (part "R-US_R0402"))
    )
    (comp (ref "R72")
      (value "698")
      (footprint "eagle-import:R0402")
      (libsource (lib "eagle-import") (part "R-US_R0402"))
    )
    (comp (ref "R73")
      (value "698")
      (footprint "eagle-import:R0402")
      (libsource (lib "eagle-import") (part "R-US_R0402"))
    )
    (comp (ref "R74")
      (value "698")
      (footprint "eagle-import:R0402")
      (libsource (lib "eagle-import") (part "R-US_R0402"))
    )
    (comp (ref "R75")
      (value "698")
      (footprint "eagle-import:R0402")
      (libsource (lib "eagle-import") (part "R-US_R0402"))
    )
    (comp (ref "R76")
      (value "698")
      (footprint "eagle-import:R0402")
      (libsource (lib "eagle-import") (part "R-US_R0402"))
    )
    (comp (ref "R77")
      (value "1k")
      (footprint "eagle-import:R0402")
      (libsource (lib "eagle-import") (part "R-US_R0402"))
    )
    (comp (ref "R78")
      (value "1k")
      (footprint "eagle-import:R0402")
      (libsource (lib "eagle-import") (part "R-US_R0402"))
    )
    (comp (ref "R79")
      (value "1k")
      (footprint "eagle-import:R0402")
      (libsource (lib "eagle-import") (part "R-US_R0402"))
    )
    (comp (ref "R81")
      (value "698")
      (footprint "eagle-import:R0402")
      (libsource (lib "eagle-import") (part "R-US_R0402"))
    )
    (comp (ref "R82")
      (value "698")
      (footprint "eagle-import:R0402")
      (libsource (lib "eagle-import") (part "R-US_R0402"))
    )
    (comp (ref "R83")
      (value "698")
      (footprint "eagle-import:R0402")
      (libsource (lib "eagle-import") (part "R-US_R0402"))
    )
    (comp (ref "R84")
      (value "698")
      (footprint "eagle-import:R0402")
      (libsource (lib "eagle-import") (part "R-US_R0402"))
    )
    (comp (ref "R86")
      (value "0R")
      (footprint "eagle-import:0402")
      (libsource (lib "eagle-import") (part "RES0402"))
    )
    (comp (ref "R89")
      (value "0R")
      (footprint "eagle-import:0402")
      (libsource (lib "eagle-import") (part "RES0402"))
    )
    (comp (ref "R90")
      (value "0R")
      (footprint "eagle-import:0402")
      (libsource (lib "eagle-import") (part "RES0402"))
    )
    (comp (ref "R91")
      (value "0R")
      (footprint "eagle-import:0402")
      (libsource (lib "eagle-import") (part "RES0402"))
    )
    (comp (ref "R92")
      (value "0R")
      (footprint "eagle-import:0402")
      (libsource (lib "eagle-import") (part "RES0402"))
    )
    (comp (ref "R93")
      (value "0R")
      (footprint "eagle-import:0402")
      (libsource (lib "eagle-import") (part "RES0402"))
    )
    (comp (ref "R94")
      (value "0R")
      (footprint "eagle-import:0402")
      (libsource (lib "eagle-import") (part "RES0402"))
    )
    (comp (ref "R95")
      (value "0R")
      (footprint "eagle-import:0402")
      (libsource (lib "eagle-import") (part "RES0402"))
    )
    (comp (ref "R96")
      (value "200")
      (footprint "eagle-import:0402")
      (libsource (lib "eagle-import") (part "RES0402"))
    )
    (comp (ref "R97")
      (value "10K")
      (footprint "eagle-import:0402")
      (libsource (lib "eagle-import") (part "RES0402"))
    )
    (comp (ref "R98")
      (value "1K")
      (footprint "eagle-import:0402")
      (libsource (lib "eagle-import") (part "RES0402"))
    )
    (comp (ref "R99")
      (value "1K")
      (footprint "eagle-import:0402")
      (libsource (lib "eagle-import") (part "RES0402"))
    )
    (comp (ref "R100")
      (value "1K")
      (footprint "eagle-import:0402")
      (libsource (lib "eagle-import") (part "RES0402"))
    )
    (comp (ref "R101")
      (value "1K")
      (footprint "eagle-import:0402")
      (libsource (lib "eagle-import") (part "RES0402"))
    )
    (comp (ref "R102")
      (value "10K")
      (footprint "eagle-import:0402")
      (libsource (lib "eagle-import") (part "RES0402"))
    )
    (comp (ref "R103")
      (value "0R")
      (footprint "eagle-import:0402")
      (libsource (lib "eagle-import") (part "RES0402"))
    )
    (comp (ref "R104")
      (value "0R")
      (footprint "eagle-import:0402")
      (libsource (lib "eagle-import") (part "RES0402"))
    )
    (comp (ref "R105")
      (value "0R")
      (footprint "eagle-import:0402")
      (libsource (lib "eagle-import") (part "RES0402"))
    )
    (comp (ref "R106")
      (value "200R")
      (footprint "eagle-import:0402")
      (libsource (lib "eagle-import") (part "RES0402"))
    )
    (comp (ref "R107")
      (value "200R")
      (footprint "eagle-import:0402")
      (libsource (lib "eagle-import") (part "RES0402"))
    )
    (comp (ref "R108")
      (value "2.2K")
      (footprint "eagle-import:0402")
      (libsource (lib "eagle-import") (part "RES0402"))
    )
    (comp (ref "R109")
      (value "4.7K")
      (footprint "eagle-import:0402")
      (libsource (lib "eagle-import") (part "RES0402"))
    )
    (comp (ref "R110")
      (value "12K")
      (footprint "eagle-import:0402")
      (libsource (lib "eagle-import") (part "RES0402"))
    )
    (comp (ref "R111")
      (value "4.7K")
      (footprint "eagle-import:0402")
      (libsource (lib "eagle-import") (part "RES0402"))
    )
    (comp (ref "R112")
      (value "4.7K")
      (footprint "eagle-import:0402")
      (libsource (lib "eagle-import") (part "RES0402"))
    )
    (comp (ref "R113")
      (value "4.7K")
      (footprint "eagle-import:0402")
      (libsource (lib "eagle-import") (part "RES0402"))
    )
    (comp (ref "R114")
      (value "120R")
      (footprint "eagle-import:0402")
      (libsource (lib "eagle-import") (part "RES0402"))
    )
    (comp (ref "R115")
      (value "100K")
      (footprint "eagle-import:0402")
      (libsource (lib "eagle-import") (part "RES0402"))
    )
    (comp (ref "TP1")
      (value "TPSB1,27")
      (footprint "eagle-import:B1,27")
      (libsource (lib "eagle-import") (part "TPSB1,27"))
    )
    (comp (ref "U$5")
      (value "USB-CON-5PIN-105017-0001")
      (footprint "eagle-import:USB-MICRO-MOLEX-105017-0001")
      (libsource (lib "eagle-import") (part "USB-CON-5PIN-105017-0001"))
    )
    (comp (ref "U1")
      (value "LM324PW")
      (footprint "eagle-import:SOP65P640X120-14N")
      (libsource (lib "eagle-import") (part "LM324PW"))
    )
    (comp (ref "U2")
      (value "TPS70445_PWP_24")
      (footprint "eagle-import:PWP24_4P68X2P4")
      (fields
        (field (name "GENERIC_PART_NUMBER") "TPS70445")
        (field (name "MANUFACTURER") "Texas Instruments")
        (field (name "MANUFACTURER_PART_NUMBER") "tps70445_pwp_24")
      )
      (libsource (lib "eagle-import") (part "TPS70445_PWP_24"))
    )
    (comp (ref "U3")
      (value "LM324PW")
      (footprint "eagle-import:SOP65P640X120-14N")
      (libsource (lib "eagle-import") (part "LM324PW"))
    )
    (comp (ref "U4")
      (value "LM324PW")
      (footprint "eagle-import:SOP65P640X120-14N")
      (libsource (lib "eagle-import") (part "LM324PW"))
    )
    (comp (ref "U5")
      (value "LM324PW")
      (footprint "eagle-import:SOP65P640X120-14N")
      (libsource (lib "eagle-import") (part "LM324PW"))
    )
    (comp (ref "U6")
      (value "LM324PW")
      (footprint "eagle-import:SOP65P640X120-14N")
      (libsource (lib "eagle-import") (part "LM324PW"))
    )
    (comp (ref "U7")
      (value "RM42L432_PZ_100RM42L432_PZ_100")
      (footprint "eagle-import:PZ100")
      (fields (field (name "MANUFACTURER_PART_NUMBER") "rm42l432_pz_100"))
      (libsource (lib "eagle-import") (part "RM42L432_PZ_100RM42L432_PZ_100"))
    )
    (comp (ref "U8")
      (value "LM324PW")
      (footprint "eagle-import:SOP65P640X120-14N")
      (libsource (lib "eagle-import") (part "LM324PW"))
    )
    (comp (ref "U9")
      (value "XC2C32A-6CP56C")
      (footprint "eagle-import:CP56")
      (libsource (lib "eagle-import") (part "XC2C32A-6CP56C"))
    )
    (comp (ref "U10")
      (value "FT2232HL")
      (footprint "eagle-import:LQFP64")
      (libsource (lib "eagle-import") (part "FT2232HL"))
    )
    (comp (ref "U11")
      (value "93LC56C-I/SN")
      (footprint "eagle-import:SO8")
      (libsource (lib "eagle-import") (part "93LC56C-I/SN"))
    )
    (comp (ref "X1")
      (value "AS14-35")
      (footprint "eagle-import:AS14-35")
      (libsource (lib "eagle-import") (part "AS14-35"))
    )
    (comp (ref "X2")
      (value "1751316")
      (footprint "eagle-import:1751316")
      (libsource (lib "eagle-import") (part "1751316"))
    )
    (comp (ref "XTAL1")
      (value "7M-16.000MAAJ-T")
      (footprint "eagle-import:TXC_7M-16.000MAAJ-T")
      (fields (field (name "MPN") "7M-16.000MAAJ-T "))
      (libsource (lib "eagle-import") (part "7M-16.000MAAJ-T"))
    )
    (comp (ref "Y1")
      (value "12M")
      (footprint "eagle-import:CRYSTAL_3225")
      (libsource (lib "eagle-import") (part "CRYSTAL-SMD"))
    )
  )
  (nets
    (net (code "1") (name "+1V2") (class "Default")
      (node (ref "C13") (pin "1") (pinfunction "1_1") (pintype "passive"))
      (node (ref "C14") (pin "1") (pinfunction "1_1") (pintype "passive"))
      (node (ref "C15") (pin "1") (pinfunction "1_1") (pintype "passive"))
      (node (ref "C16") (pin "1") (pinfunction "1_1") (pintype "passive"))
      (node (ref "C17") (pin "1") (pinfunction "1_1") (pintype "passive"))
      (node (ref "C18") (pin "1") (pinfunction "1_1") (pintype "passive"))
      (node (ref "C20") (pin "1") (pinfunction "1_1") (pintype "passive"))
      (node (ref "C4") (pin "-") (pinfunction "+_-") (pintype "passive"))
      (node (ref "U2") (pin "14") (pinfunction "VOUT2_2_14") (pintype "output"))
      (node (ref "U2") (pin "15") (pinfunction "VOUT2_15") (pintype "output"))
      (node (ref "U2") (pin "16") (pinfunction "VSENSE2/FB2_16") (pintype "input"))
      (node (ref "U7") (pin "21") (pinfunction "VCC_2_21") (pintype "power_in"))
      (node (ref "U7") (pin "30") (pinfunction "VCC_3_30") (pintype "power_in"))
      (node (ref "U7") (pin "32") (pinfunction "VCC_4_32") (pintype "power_in"))
      (node (ref "U7") (pin "61") (pinfunction "VCC_5_61") (pintype "power_in"))
      (node (ref "U7") (pin "88") (pinfunction "VCC_6_88") (pintype "power_in"))
      (node (ref "U7") (pin "99") (pinfunction "VCC_99") (pintype "power_in"))
    )
    (net (code "2") (name "+1V8") (class "Default")
      (node (ref "C54") (pin "1") (pinfunction "1_1") (pintype "passive"))
      (node (ref "C56") (pin "1") (pinfunction "1_1") (pintype "passive"))
      (node (ref "C61") (pin "1") (pinfunction "1_1") (pintype "passive"))
      (node (ref "C62") (pin "1") (pinfunction "1_1") (pintype "passive"))
      (node (ref "C63") (pin "1") (pinfunction "1_1") (pintype "passive"))
      (node (ref "U10") (pin "12") (pinfunction "VCORE1_12") (pintype "bidirectional"))
      (node (ref "U10") (pin "37") (pinfunction "VCORE2_37") (pintype "bidirectional"))
      (node (ref "U10") (pin "49") (pinfunction "VREGOUT_49") (pintype "bidirectional"))
      (node (ref "U10") (pin "64") (pinfunction "VCORE3_64") (pintype "bidirectional"))
      (node (ref "U9") (pin "G8") (pinfunction "VCC1V8_G8") (pintype "bidirectional"))
    )
    (net (code "3") (name "+3V3") (class "Default")
      (node (ref "C19") (pin "1") (pinfunction "1_1") (pintype "passive"))
      (node (ref "C21") (pin "1") (pinfunction "1_1") (pintype "passive"))
      (node (ref "C22") (pin "1") (pinfunction "1_1") (pintype "passive"))
      (node (ref "C23") (pin "1") (pinfunction "1_1") (pintype "passive"))
      (node (ref "C24") (pin "1") (pinfunction "1_1") (pintype "passive"))
      (node (ref "C25") (pin "1") (pinfunction "1_1") (pintype "passive"))
      (node (ref "C26") (pin "1") (pinfunction "1_1") (pintype "passive"))
      (node (ref "C3") (pin "-") (pinfunction "+_-") (pintype "passive"))
      (node (ref "C46") (pin "1") (pinfunction "1_1") (pintype "passive"))
      (node (ref "C52") (pin "1") (pinfunction "1_1") (pintype "passive"))
      (node (ref "C53") (pin "1") (pinfunction "1_1") (pintype "passive"))
      (node (ref "C55") (pin "1") (pinfunction "1_1") (pintype "passive"))
      (node (ref "C57") (pin "1") (pinfunction "1_1") (pintype "passive"))
      (node (ref "C60") (pin "1") (pinfunction "1_1") (pintype "passive"))
      (node (ref "C64") (pin "1") (pinfunction "1_1") (pintype "passive"))
      (node (ref "C65") (pin "1") (pinfunction "1_1") (pintype "passive"))
      (node (ref "C66") (pin "1") (pinfunction "1_1") (pintype "passive"))
      (node (ref "C67") (pin "1") (pinfunction "1_1") (pintype "passive"))
      (node (ref "C68") (pin "1") (pinfunction "1_1") (pintype "passive"))
      (node (ref "C7") (pin "1") (pinfunction "1_1") (pintype "passive"))
      (node (ref "C73") (pin "1") (pinfunction "1_1") (pintype "passive"))
      (node (ref "C76") (pin "1") (pinfunction "1_1") (pintype "passive"))
      (node (ref "D27") (pin "A") (pinfunction "A_A") (pintype "passive"))
      (node (ref "D28") (pin "A") (pinfunction "A_A") (pintype "passive"))
      (node (ref "FB1") (pin "1") (pinfunction "1_1") (pintype "passive"))
      (node (ref "FB2") (pin "1") (pinfunction "1_1") (pintype "passive"))
      (node (ref "IC1") (pin "1") (pinfunction "VCC1_1") (pintype "input"))
      (node (ref "IC2") (pin "1") (pinfunction "VCC1_1") (pintype "input"))
      (node (ref "Q1") (pin "2") (pinfunction "S_2") (pintype "passive"))
      (node (ref "Q3") (pin "2") (pinfunction "S_2") (pintype "passive"))
      (node (ref "R1") (pin "2") (pinfunction "2_2") (pintype "passive"))
      (node (ref "R100") (pin "1") (pinfunction "1_1") (pintype "passive"))
      (node (ref "R101") (pin "1") (pinfunction "1_1") (pintype "passive"))
      (node (ref "R109") (pin "1") (pinfunction "1_1") (pintype "passive"))
      (node (ref "R111") (pin "2") (pinfunction "2_2") (pintype "passive"))
      (node (ref "R112") (pin "2") (pinfunction "2_2") (pintype "passive"))
      (node (ref "R113") (pin "2") (pinfunction "2_2") (pintype "passive"))
      (node (ref "R115") (pin "2") (pinfunction "2_2") (pintype "passive"))
      (node (ref "R2") (pin "2") (pinfunction "2_2") (pintype "passive"))
      (node (ref "R60") (pin "2") (pinfunction "2_2") (pintype "passive"))
      (node (ref "R7") (pin "2") (pinfunction "2_2") (pintype "passive"))
      (node (ref "R96") (pin "1") (pinfunction "1_1") (pintype "passive"))
      (node (ref "R97") (pin "2") (pinfunction "2_2") (pintype "passive"))
      (node (ref "R98") (pin "1") (pinfunction "1_1") (pintype "passive"))
      (node (ref "R99") (pin "1") (pinfunction "1_1") (pintype "passive"))
      (node (ref "U10") (pin "20") (pinfunction "VCCIO1_20") (pintype "bidirectional"))
      (node (ref "U10") (pin "31") (pinfunction "VCCIO2_31") (pintype "bidirectional"))
      (node (ref "U10") (pin "42") (pinfunction "VCCIO3_42") (pintype "bidirectional"))
      (node (ref "U10") (pin "50") (pinfunction "VREGIN_50") (pintype "bidirectional"))
      (node (ref "U10") (pin "56") (pinfunction "VCCIO4_56") (pintype "bidirectional"))
      (node (ref "U11") (pin "6") (pinfunction "ORG_6") (pintype "bidirectional"))
      (node (ref "U11") (pin "8") (pinfunction "VCC_8") (pintype "bidirectional"))
      (node (ref "U2") (pin "21") (pinfunction "VSENSE1/FB1_21") (pintype "input"))
      (node (ref "U2") (pin "22") (pinfunction "VOUT1_2_22") (pintype "output"))
      (node (ref "U2") (pin "23") (pinfunction "VOUT1_23") (pintype "output"))
      (node (ref "U7") (pin "13") (pinfunction "VCCIO_3_13") (pintype "power_in"))
      (node (ref "U7") (pin "28") (pinfunction "VCCIO_4_28") (pintype "power_in"))
      (node (ref "U7") (pin "46") (pinfunction "VCCAD/ADREFHI_46") (pintype "bidirectional"))
      (node (ref "U7") (pin "6") (pinfunction "VCCIO_2_6") (pintype "power_in"))
      (node (ref "U7") (pin "60") (pinfunction "VCCIO_5_60") (pintype "power_in"))
      (node (ref "U7") (pin "85") (pinfunction "VCCIO_85") (pintype "power_in"))
      (node (ref "U7") (pin "96") (pinfunction "VCCP_96") (pintype "power_in"))
      (node (ref "U9") (pin "C6") (pinfunction "VCCIO2_C6") (pintype "bidirectional"))
      (node (ref "U9") (pin "D3") (pinfunction "VCCAUX_D3") (pintype "bidirectional"))
      (node (ref "U9") (pin "H6") (pinfunction "VCCIO1_H6") (pintype "bidirectional"))
    )
    (net (code "4") (name "+5V") (class "Default")
      (node (ref "C1") (pin "1") (pinfunction "1_1") (pintype "passive"))
      (node (ref "C10") (pin "1") (pinfunction "1_1") (pintype "passive"))
      (node (ref "C2") (pin "1") (pinfunction "1_1") (pintype "passive"))
      (node (ref "C5") (pin "-") (pinfunction "+_-") (pintype "passive"))
      (node (ref "C6") (pin "1") (pinfunction "1_1") (pintype "passive"))
      (node (ref "C74") (pin "1") (pinfunction "1_1") (pintype "passive"))
      (node (ref "C9") (pin "1") (pinfunction "1_1") (pintype "passive"))
      (node (ref "D1") (pin "1") (pinfunction "1_1") (pintype "passive"))
      (node (ref "D37") (pin "2") (pinfunction "2_2") (pintype "passive"))
      (node (ref "F1") (pin "2") (pinfunction "2_2") (pintype "passive"))
      (node (ref "IC1") (pin "8") (pinfunction "VCC2_8") (pintype "input"))
      (node (ref "IC2") (pin "8") (pinfunction "VCC2_8") (pintype "input"))
      (node (ref "R3") (pin "2") (pinfunction "2_2") (pintype "passive"))
      (node (ref "U1") (pin "4") (pinfunction "VCC_4") (pintype "power_in"))
      (node (ref "U2") (pin "10") (pinfunction "VIN2_2_10") (pintype "input"))
      (node (ref "U2") (pin "11") (pinfunction "VIN2_11") (pintype "input"))
      (node (ref "U2") (pin "2") (pinfunction "VIN1_2_2") (pintype "input"))
      (node (ref "U2") (pin "3") (pinfunction "VIN1_3") (pintype "input"))
      (node (ref "U3") (pin "4") (pinfunction "VCC_4") (pintype "power_in"))
      (node (ref "U4") (pin "4") (pinfunction "VCC_4") (pintype "power_in"))
      (node (ref "U5") (pin "4") (pinfunction "VCC_4") (pintype "power_in"))
      (node (ref "U6") (pin "4") (pinfunction "VCC_4") (pintype "power_in"))
      (node (ref "U8") (pin "4") (pinfunction "VCC_4") (pintype "power_in"))
      (node (ref "X2") (pin "1") (pinfunction "K_1") (pintype "passive"))
    )
    (net (code "5") (name "/5V_IN") (class "Default")
      (node (ref "F1") (pin "1") (pinfunction "1_1") (pintype "passive"))
      (node (ref "U$5") (pin "1") (pinfunction "VBUS_1") (pintype "power_in"))
      (node (ref "X1") (pin "1") (pinfunction "1_1") (pintype "passive"))
      (node (ref "X2") (pin "7") (pinfunction "K_7") (pintype "passive"))
    )
    (net (code "6") (name "/A0_3V3") (class "Default")
      (node (ref "R8") (pin "1") (pinfunction "1_1") (pintype "passive"))
      (node (ref "R9") (pin "2") (pinfunction "2_2") (pintype "passive"))
      (node (ref "U3") (pin "3") (pinfunction "1IN+_3") (pintype "input"))
    )
    (net (code "7") (name "/A0_BUFFERED") (class "Default")
      (node (ref "U3") (pin "1") (pinfunction "1OUT_1") (pintype "output"))
      (node (ref "U3") (pin "2") (pinfunction "1IN-_2") (pintype "input"))
      (node (ref "U7") (pin "42") (pinfunction "ADIN[0]_42") (pintype "bidirectional"))
    )
    (net (code "8") (name "/A0_IN") (class "Default")
      (node (ref "D4") (pin "2") (pinfunction "2_2") (pintype "passive"))
      (node (ref "R62") (pin "2") (pinfunction "2_2") (pintype "passive"))
      (node (ref "X1") (pin "7") (pinfunction "1_7") (pintype "passive"))
    )
    (net (code "9") (name "/A1_3V3") (class "Default")
      (node (ref "R10") (pin "1") (pinfunction "1_1") (pintype "passive"))
      (node (ref "R11") (pin "2") (pinfunction "2_2") (pintype "passive"))
      (node (ref "U3") (pin "5") (pinfunction "2IN+_5") (pintype "input"))
    )
    (net (code "10") (name "/A1_BUFFERED") (class "Default")
      (node (ref "U3") (pin "6") (pinfunction "2IN-_6") (pintype "input"))
      (node (ref "U3") (pin "7") (pinfunction "2OUT_7") (pintype "output"))
      (node (ref "U7") (pin "49") (pinfunction "ADIN[1]_49") (pintype "bidirectional"))
    )
    (net (code "11") (name "/A1_IN") (class "Default")
      (node (ref "D5") (pin "2") (pinfunction "2_2") (pintype "passive"))
      (node (ref "R73") (pin "2") (pinfunction "2_2") (pintype "passive"))
      (node (ref "X1") (pin "8") (pinfunction "1_8") (pintype "passive"))
    )
    (net (code "12") (name "/A2_3V3") (class "Default")
      (node (ref "R12") (pin "1") (pinfunction "1_1") (pintype "passive"))
      (node (ref "R13") (pin "2") (pinfunction "2_2") (pintype "passive"))
      (node (ref "U3") (pin "10") (pinfunction "3IN+_10") (pintype "input"))
    )
    (net (code "13") (name "/A2_BUFFERED") (class "Default")
      (node (ref "U3") (pin "8") (pinfunction "3OUT_8") (pintype "output"))
      (node (ref "U3") (pin "9") (pinfunction "3IN-_9") (pintype "input"))
      (node (ref "U7") (pin "51") (pinfunction "ADIN[2]_51") (pintype "bidirectional"))
    )
    (net (code "14") (name "/A2_IN") (class "Default")
      (node (ref "D6") (pin "2") (pinfunction "2_2") (pintype "passive"))
      (node (ref "R61") (pin "2") (pinfunction "2_2") (pintype "passive"))
      (node (ref "X1") (pin "9") (pinfunction "1_9") (pintype "passive"))
      (node (ref "X2") (pin "4") (pinfunction "K_4") (pintype "passive"))
    )
    (net (code "15") (name "/A3_3V3") (class "Default")
      (node (ref "R14") (pin "1") (pinfunction "1_1") (pintype "passive"))
      (node (ref "R15") (pin "2") (pinfunction "2_2") (pintype "passive"))
      (node (ref "U3") (pin "12") (pinfunction "4IN+_12") (pintype "input"))
    )
    (net (code "16") (name "/A3_BUFFERED") (class "Default")
      (node (ref "U3") (pin "13") (pinfunction "4IN-_13") (pintype "input"))
      (node (ref "U3") (pin "14") (pinfunction "4OUT_14") (pintype "output"))
      (node (ref "U7") (pin "52") (pinfunction "ADIN[3]_52") (pintype "bidirectional"))
    )
    (net (code "17") (name "/A3_IN") (class "Default")
      (node (ref "D30") (pin "2") (pinfunction "2_2") (pintype "passive"))
      (node (ref "R84") (pin "2") (pinfunction "2_2") (pintype "passive"))
      (node (ref "X1") (pin "10") (pinfunction "1_10") (pintype "passive"))
      (node (ref "X2") (pin "3") (pinfunction "K_3") (pintype "passive"))
    )
    (net (code "18") (name "/A4_3V3") (class "Default")
      (node (ref "R16") (pin "1") (pinfunction "1_1") (pintype "passive"))
      (node (ref "R17") (pin "2") (pinfunction "2_2") (pintype "passive"))
      (node (ref "U4") (pin "3") (pinfunction "1IN+_3") (pintype "input"))
    )
    (net (code "19") (name "/A4_BUFFERED") (class "Default")
      (node (ref "U4") (pin "1") (pinfunction "1OUT_1") (pintype "output"))
      (node (ref "U4") (pin "2") (pinfunction "1IN-_2") (pintype "input"))
      (node (ref "U7") (pin "54") (pinfunction "ADIN[4]_54") (pintype "bidirectional"))
    )
    (net (code "20") (name "/A4_IN") (class "Default")
      (node (ref "D10") (pin "2") (pinfunction "2_2") (pintype "passive"))
      (node (ref "R63") (pin "2") (pinfunction "2_2") (pintype "passive"))
      (node (ref "X1") (pin "11") (pinfunction "1_11") (pintype "passive"))
    )
    (net (code "21") (name "/A5_3V3") (class "Default")
      (node (ref "R18") (pin "1") (pinfunction "1_1") (pintype "passive"))
      (node (ref "R19") (pin "2") (pinfunction "2_2") (pintype "passive"))
      (node (ref "U4") (pin "5") (pinfunction "2IN+_5") (pintype "input"))
    )
    (net (code "22") (name "/A5_BUFFERED") (class "Default")
      (node (ref "U4") (pin "6") (pinfunction "2IN-_6") (pintype "input"))
      (node (ref "U4") (pin "7") (pinfunction "2OUT_7") (pintype "output"))
      (node (ref "U7") (pin "55") (pinfunction "ADIN[5]_55") (pintype "bidirectional"))
    )
    (net (code "23") (name "/A5_IN") (class "Default")
      (node (ref "D11") (pin "2") (pinfunction "2_2") (pintype "passive"))
      (node (ref "R72") (pin "2") (pinfunction "2_2") (pintype "passive"))
      (node (ref "X1") (pin "12") (pinfunction "1_12") (pintype "passive"))
    )
    (net (code "24") (name "/A6_3V3") (class "Default")
      (node (ref "R20") (pin "1") (pinfunction "1_1") (pintype "passive"))
      (node (ref "R21") (pin "2") (pinfunction "2_2") (pintype "passive"))
      (node (ref "U4") (pin "10") (pinfunction "3IN+_10") (pintype "input"))
    )
    (net (code "25") (name "/A6_BUFFERED") (class "Default")
      (node (ref "U4") (pin "8") (pinfunction "3OUT_8") (pintype "output"))
      (node (ref "U4") (pin "9") (pinfunction "3IN-_9") (pintype "input"))
      (node (ref "U7") (pin "56") (pinfunction "ADIN[6]_56") (pintype "bidirectional"))
    )
    (net (code "26") (name "/A6_IN") (class "Default")
      (node (ref "D12") (pin "2") (pinfunction "2_2") (pintype "passive"))
      (node (ref "R74") (pin "2") (pinfunction "2_2") (pintype "passive"))
      (node (ref "X1") (pin "13") (pinfunction "1_13") (pintype "passive"))
    )
    (net (code "27") (name "/A7_3V3") (class "Default")
      (node (ref "R22") (pin "1") (pinfunction "1_1") (pintype "passive"))
      (node (ref "R23") (pin "2") (pinfunction "2_2") (pintype "passive"))
      (node (ref "U4") (pin "12") (pinfunction "4IN+_12") (pintype "input"))
    )
    (net (code "28") (name "/A7_BUFFERED") (class "Default")
      (node (ref "U4") (pin "13") (pinfunction "4IN-_13") (pintype "input"))
      (node (ref "U4") (pin "14") (pinfunction "4OUT_14") (pintype "output"))
      (node (ref "U7") (pin "43") (pinfunction "ADIN[7]_43") (pintype "bidirectional"))
    )
    (net (code "29") (name "/A7_IN") (class "Default")
      (node (ref "D33") (pin "2") (pinfunction "2_2") (pintype "passive"))
      (node (ref "R83") (pin "2") (pinfunction "2_2") (pintype "passive"))
      (node (ref "X1") (pin "14") (pinfunction "1_14") (pintype "passive"))
    )
    (net (code "30") (name "/A8_3V3") (class "Default")
      (node (ref "R24") (pin "1") (pinfunction "1_1") (pintype "passive"))
      (node (ref "R25") (pin "2") (pinfunction "2_2") (pintype "passive"))
      (node (ref "U5") (pin "3") (pinfunction "1IN+_3") (pintype "input"))
    )
    (net (code "31") (name "/A8_BUFFERED") (class "Default")
      (node (ref "U5") (pin "1") (pinfunction "1OUT_1") (pintype "output"))
      (node (ref "U5") (pin "2") (pinfunction "1IN-_2") (pintype "input"))
      (node (ref "U7") (pin "57") (pinfunction "ADIN[8]_57") (pintype "bidirectional"))
    )
    (net (code "32") (name "/A8_IN") (class "Default")
      (node (ref "D13") (pin "2") (pinfunction "2_2") (pintype "passive"))
      (node (ref "R64") (pin "2") (pinfunction "2_2") (pintype "passive"))
      (node (ref "X1") (pin "15") (pinfunction "1_15") (pintype "passive"))
    )
    (net (code "33") (name "/A9_3V3") (class "Default")
      (node (ref "R26") (pin "1") (pinfunction "1_1") (pintype "passive"))
      (node (ref "R27") (pin "2") (pinfunction "2_2") (pintype "passive"))
      (node (ref "U5") (pin "5") (pinfunction "2IN+_5") (pintype "input"))
    )
    (net (code "34") (name "/A9_BUFFERED") (class "Default")
      (node (ref "U5") (pin "6") (pinfunction "2IN-_6") (pintype "input"))
      (node (ref "U5") (pin "7") (pinfunction "2OUT_7") (pintype "output"))
      (node (ref "U7") (pin "48") (pinfunction "ADIN[9]_48") (pintype "bidirectional"))
    )
    (net (code "35") (name "/A9_IN") (class "Default")
      (node (ref "D14") (pin "2") (pinfunction "2_2") (pintype "passive"))
      (node (ref "R71") (pin "2") (pinfunction "2_2") (pintype "passive"))
      (node (ref "X1") (pin "16") (pinfunction "1_16") (pintype "passive"))
    )
    (net (code "36") (name "/A10_3V3") (class "Default")
      (node (ref "R28") (pin "1") (pinfunction "1_1") (pintype "passive"))
      (node (ref "R29") (pin "2") (pinfunction "2_2") (pintype "passive"))
      (node (ref "U5") (pin "10") (pinfunction "3IN+_10") (pintype "input"))
    )
    (net (code "37") (name "/A10_BUFFERED") (class "Default")
      (node (ref "U5") (pin "8") (pinfunction "3OUT_8") (pintype "output"))
      (node (ref "U5") (pin "9") (pinfunction "3IN-_9") (pintype "input"))
      (node (ref "U7") (pin "50") (pinfunction "ADIN[10]_50") (pintype "bidirectional"))
    )
    (net (code "38") (name "/A10_IN") (class "Default")
      (node (ref "D15") (pin "2") (pinfunction "2_2") (pintype "passive"))
      (node (ref "R75") (pin "2") (pinfunction "2_2") (pintype "passive"))
      (node (ref "X1") (pin "17") (pinfunction "1_17") (pintype "passive"))
    )
    (net (code "39") (name "/A11_3V3") (class "Default")
      (node (ref "R30") (pin "1") (pinfunction "1_1") (pintype "passive"))
      (node (ref "R31") (pin "2") (pinfunction "2_2") (pintype "passive"))
      (node (ref "U5") (pin "12") (pinfunction "4IN+_12") (pintype "input"))
    )
    (net (code "40") (name "/A11_BUFFERED") (class "Default")
      (node (ref "U5") (pin "13") (pinfunction "4IN-_13") (pintype "input"))
      (node (ref "U5") (pin "14") (pinfunction "4OUT_14") (pintype "output"))
      (node (ref "U7") (pin "53") (pinfunction "ADIN[11]_53") (pintype "bidirectional"))
    )
    (net (code "41") (name "/A11_IN") (class "Default")
      (node (ref "D32") (pin "2") (pinfunction "2_2") (pintype "passive"))
      (node (ref "R82") (pin "2") (pinfunction "2_2") (pintype "passive"))
      (node (ref "X1") (pin "18") (pinfunction "1_18") (pintype "passive"))
    )
    (net (code "42") (name "/A12_3V3") (class "Default")
      (node (ref "R32") (pin "1") (pinfunction "1_1") (pintype "passive"))
      (node (ref "R33") (pin "2") (pinfunction "2_2") (pintype "passive"))
      (node (ref "U6") (pin "3") (pinfunction "1IN+_3") (pintype "input"))
    )
    (net (code "43") (name "/A12_BUFFERED") (class "Default")
      (node (ref "U6") (pin "1") (pinfunction "1OUT_1") (pintype "output"))
      (node (ref "U6") (pin "2") (pinfunction "1IN-_2") (pintype "input"))
      (node (ref "U7") (pin "40") (pinfunction "ADIN[16]_40") (pintype "bidirectional"))
    )
    (net (code "44") (name "/A12_IN") (class "Default")
      (node (ref "D16") (pin "2") (pinfunction "2_2") (pintype "passive"))
      (node (ref "R65") (pin "2") (pinfunction "2_2") (pintype "passive"))
      (node (ref "X1") (pin "19") (pinfunction "1_19") (pintype "passive"))
    )
    (net (code "45") (name "/A13_3V3") (class "Default")
      (node (ref "R34") (pin "1") (pinfunction "1_1") (pintype "passive"))
      (node (ref "R35") (pin "2") (pinfunction "2_2") (pintype "passive"))
      (node (ref "U6") (pin "5") (pinfunction "2IN+_5") (pintype "input"))
    )
    (net (code "46") (name "/A13_BUFFERED") (class "Default")
      (node (ref "U6") (pin "6") (pinfunction "2IN-_6") (pintype "input"))
      (node (ref "U6") (pin "7") (pinfunction "2OUT_7") (pintype "output"))
      (node (ref "U7") (pin "41") (pinfunction "ADIN[17]_41") (pintype "bidirectional"))
    )
    (net (code "47") (name "/A13_IN") (class "Default")
      (node (ref "D17") (pin "2") (pinfunction "2_2") (pintype "passive"))
      (node (ref "R70") (pin "2") (pinfunction "2_2") (pintype "passive"))
      (node (ref "X1") (pin "20") (pinfunction "1_20") (pintype "passive"))
    )
    (net (code "48") (name "/A14_3V3") (class "Default")
      (node (ref "R36") (pin "1") (pinfunction "1_1") (pintype "passive"))
      (node (ref "R37") (pin "2") (pinfunction "2_2") (pintype "passive"))
      (node (ref "U6") (pin "10") (pinfunction "3IN+_10") (pintype "input"))
    )
    (net (code "49") (name "/A14_BUFFERED") (class "Default")
      (node (ref "U6") (pin "8") (pinfunction "3OUT_8") (pintype "output"))
      (node (ref "U6") (pin "9") (pinfunction "3IN-_9") (pintype "input"))
      (node (ref "U7") (pin "44") (pinfunction "ADIN[20]_44") (pintype "bidirectional"))
    )
    (net (code "50") (name "/A14_IN") (class "Default")
      (node (ref "D18") (pin "2") (pinfunction "2_2") (pintype "passive"))
      (node (ref "R76") (pin "2") (pinfunction "2_2") (pintype "passive"))
      (node (ref "X1") (pin "21") (pinfunction "1_21") (pintype "passive"))
    )
    (net (code "51") (name "/A15_3V3") (class "Default")
      (node (ref "R38") (pin "1") (pinfunction "1_1") (pintype "passive"))
      (node (ref "R39") (pin "2") (pinfunction "2_2") (pintype "passive"))
      (node (ref "U6") (pin "12") (pinfunction "4IN+_12") (pintype "input"))
    )
    (net (code "52") (name "/A15_BUFFERED") (class "Default")
      (node (ref "U6") (pin "13") (pinfunction "4IN-_13") (pintype "input"))
      (node (ref "U6") (pin "14") (pinfunction "4OUT_14") (pintype "output"))
      (node (ref "U7") (pin "45") (pinfunction "ADIN[21]_45") (pintype "bidirectional"))
    )
    (net (code "53") (name "/A15_IN") (class "Default")
      (node (ref "D31") (pin "2") (pinfunction "2_2") (pintype "passive"))
      (node (ref "R81") (pin "2") (pinfunction "2_2") (pintype "passive"))
      (node (ref "X1") (pin "22") (pinfunction "1_22") (pintype "passive"))
    )
    (net (code "54") (name "/CAN1H") (class "Default")
      (node (ref "D25") (pin "1") (pinfunction "1_1") (pintype "passive"))
      (node (ref "IC1") (pin "7") (pinfunction "CANH_7") (pintype "input"))
      (node (ref "R5") (pin "2") (pinfunction "2_2") (pintype "passive"))
      (node (ref "X1") (pin "3") (pinfunction "1_3") (pintype "passive"))
      (node (ref "X2") (pin "6") (pinfunction "K_6") (pintype "passive"))
    )
    (net (code "55") (name "/CAN1L") (class "Default")
      (node (ref "D9") (pin "2") (pinfunction "2_2") (pintype "passive"))
      (node (ref "IC1") (pin "6") (pinfunction "CANL_6") (pintype "input"))
      (node (ref "R5") (pin "1") (pinfunction "1_1") (pintype "passive"))
      (node (ref "X1") (pin "4") (pinfunction "1_4") (pintype "passive"))
      (node (ref "X2") (pin "5") (pinfunction "K_5") (pintype "passive"))
    )
    (net (code "56") (name "/CAN2H") (class "Default")
      (node (ref "D8") (pin "1") (pinfunction "1_1") (pintype "passive"))
      (node (ref "IC2") (pin "7") (pinfunction "CANH_7") (pintype "input"))
      (node (ref "R6") (pin "2") (pinfunction "2_2") (pintype "passive"))
      (node (ref "X1") (pin "5") (pinfunction "1_5") (pintype "passive"))
    )
    (net (code "57") (name "/CAN2L") (class "Default")
      (node (ref "D7") (pin "2") (pinfunction "2_2") (pintype "passive"))
      (node (ref "IC2") (pin "6") (pinfunction "CANL_6") (pintype "input"))
      (node (ref "R6") (pin "1") (pinfunction "1_1") (pintype "passive"))
      (node (ref "X1") (pin "6") (pinfunction "1_6") (pintype "passive"))
    )
    (net (code "58") (name "/CGND") (class "Default")
      (node (ref "R59") (pin "2") (pinfunction "2_2") (pintype "passive"))
    )
    (net (code "59") (name "/CPLD_TCK") (class "Default")
      (node (ref "U10") (pin "52") (pinfunction "BCBUS1_52") (pintype "bidirectional"))
      (node (ref "U9") (pin "K10") (pinfunction "TCK_K10") (pintype "bidirectional"))
    )
    (net (code "60") (name "/CPLD_TDI") (class "Default")
      (node (ref "U10") (pin "53") (pinfunction "BCBUS2_53") (pintype "bidirectional"))
      (node (ref "U9") (pin "J10") (pinfunction "TDI_J10") (pintype "bidirectional"))
    )
    (net (code "61") (name "/CPLD_TDO") (class "Default")
      (node (ref "U10") (pin "57") (pinfunction "BCBUS5_57") (pintype "bidirectional"))
      (node (ref "U9") (pin "A6") (pinfunction "TDO_A6") (pintype "bidirectional"))
    )
    (net (code "62") (name "/CPLD_TMS") (class "Default")
      (node (ref "U10") (pin "58") (pinfunction "BCBUS6_58") (pintype "bidirectional"))
      (node (ref "U9") (pin "K9") (pinfunction "TMS_K9") (pintype "bidirectional"))
    )
    (net (code "63") (name "/D0_3V3") (class "Default")
      (node (ref "R43") (pin "1") (pinfunction "1_1") (pintype "passive"))
      (node (ref "R44") (pin "2") (pinfunction "2_2") (pintype "passive"))
      (node (ref "U1") (pin "3") (pinfunction "1IN+_3") (pintype "input"))
    )
    (net (code "64") (name "/D0_BUFFERED") (class "Default")
      (node (ref "U1") (pin "1") (pinfunction "1OUT_1") (pintype "output"))
      (node (ref "U1") (pin "2") (pinfunction "1IN-_2") (pintype "input"))
      (node (ref "U7") (pin "1") (pinfunction "GIOA[0]/INT[0]_1") (pintype "bidirectional"))
    )
    (net (code "65") (name "/D0_IN") (class "Default")
      (node (ref "D19") (pin "2") (pinfunction "2_2") (pintype "passive"))
      (node (ref "R66") (pin "2") (pinfunction "2_2") (pintype "passive"))
      (node (ref "X1") (pin "23") (pinfunction "1_23") (pintype "passive"))
    )
    (net (code "66") (name "/D1_3V3") (class "Default")
      (node (ref "R45") (pin "1") (pinfunction "1_1") (pintype "passive"))
      (node (ref "R46") (pin "2") (pinfunction "2_2") (pintype "passive"))
      (node (ref "U1") (pin "5") (pinfunction "2IN+_5") (pintype "input"))
    )
    (net (code "67") (name "/D1_BUFFERED") (class "Default")
      (node (ref "U1") (pin "6") (pinfunction "2IN-_6") (pintype "input"))
      (node (ref "U1") (pin "7") (pinfunction "2OUT_7") (pintype "output"))
      (node (ref "U7") (pin "2") (pinfunction "GIOA[1]/INT[1]_2") (pintype "bidirectional"))
    )
    (net (code "68") (name "/D1_IN") (class "Default")
      (node (ref "D20") (pin "2") (pinfunction "2_2") (pintype "passive"))
      (node (ref "R40") (pin "2") (pinfunction "2_2") (pintype "passive"))
      (node (ref "X1") (pin "24") (pinfunction "1_24") (pintype "passive"))
    )
    (net (code "69") (name "/D2_3V3") (class "Default")
      (node (ref "R47") (pin "1") (pinfunction "1_1") (pintype "passive"))
      (node (ref "R48") (pin "2") (pinfunction "2_2") (pintype "passive"))
      (node (ref "U1") (pin "10") (pinfunction "3IN+_10") (pintype "input"))
    )
    (net (code "70") (name "/D2_BUFFERED") (class "Default")
      (node (ref "U1") (pin "8") (pinfunction "3OUT_8") (pintype "output"))
      (node (ref "U1") (pin "9") (pinfunction "3IN-_9") (pintype "input"))
      (node (ref "U7") (pin "5") (pinfunction "GIOA[2]/INT[2]_5") (pintype "bidirectional"))
    )
    (net (code "71") (name "/D2_IN") (class "Default")
      (node (ref "D21") (pin "2") (pinfunction "2_2") (pintype "passive"))
      (node (ref "R67") (pin "2") (pinfunction "2_2") (pintype "passive"))
      (node (ref "X1") (pin "25") (pinfunction "1_25") (pintype "passive"))
    )
    (net (code "72") (name "/D3_3V3") (class "Default")
      (node (ref "R49") (pin "1") (pinfunction "1_1") (pintype "passive"))
      (node (ref "R50") (pin "2") (pinfunction "2_2") (pintype "passive"))
      (node (ref "U1") (pin "12") (pinfunction "4IN+_12") (pintype "input"))
    )
    (net (code "73") (name "/D3_BUFFERED") (class "Default")
      (node (ref "U1") (pin "13") (pinfunction "4IN-_13") (pintype "input"))
      (node (ref "U1") (pin "14") (pinfunction "4OUT_14") (pintype "output"))
      (node (ref "U7") (pin "8") (pinfunction "GIOA[3]/INT[3]_8") (pintype "bidirectional"))
    )
    (net (code "74") (name "/D3_IN") (class "Default")
      (node (ref "D34") (pin "2") (pinfunction "2_2") (pintype "passive"))
      (node (ref "R79") (pin "2") (pinfunction "2_2") (pintype "passive"))
      (node (ref "X1") (pin "26") (pinfunction "1_26") (pintype "passive"))
    )
    (net (code "75") (name "/D4_3V3") (class "Default")
      (node (ref "R51") (pin "1") (pinfunction "1_1") (pintype "passive"))
      (node (ref "R52") (pin "2") (pinfunction "2_2") (pintype "passive"))
      (node (ref "U8") (pin "3") (pinfunction "1IN+_3") (pintype "input"))
    )
    (net (code "76") (name "/D4_BUFFERED") (class "Default")
      (node (ref "U7") (pin "9") (pinfunction "GIOA[4]/INT[4]_9") (pintype "bidirectional"))
      (node (ref "U8") (pin "1") (pinfunction "1OUT_1") (pintype "output"))
      (node (ref "U8") (pin "2") (pinfunction "1IN-_2") (pintype "input"))
    )
    (net (code "77") (name "/D4_IN") (class "Default")
      (node (ref "D22") (pin "2") (pinfunction "2_2") (pintype "passive"))
      (node (ref "R68") (pin "2") (pinfunction "2_2") (pintype "passive"))
      (node (ref "X1") (pin "27") (pinfunction "1_27") (pintype "passive"))
      (node (ref "X2") (pin "9") (pinfunction "K_9") (pintype "passive"))
    )
    (net (code "78") (name "/D5_3V3") (class "Default")
      (node (ref "R53") (pin "1") (pinfunction "1_1") (pintype "passive"))
      (node (ref "R54") (pin "2") (pinfunction "2_2") (pintype "passive"))
      (node (ref "U8") (pin "5") (pinfunction "2IN+_5") (pintype "input"))
    )
    (net (code "79") (name "/D5_BUFFERED") (class "Default")
      (node (ref "U7") (pin "10") (pinfunction "GIOA[5]/INT[5]_10") (pintype "bidirectional"))
      (node (ref "U8") (pin "6") (pinfunction "2IN-_6") (pintype "input"))
      (node (ref "U8") (pin "7") (pinfunction "2OUT_7") (pintype "output"))
    )
    (net (code "80") (name "/D5_IN") (class "Default")
      (node (ref "D23") (pin "2") (pinfunction "2_2") (pintype "passive"))
      (node (ref "R69") (pin "2") (pinfunction "2_2") (pintype "passive"))
      (node (ref "X1") (pin "28") (pinfunction "1_28") (pintype "passive"))
      (node (ref "X2") (pin "8") (pinfunction "K_8") (pintype "passive"))
    )
    (net (code "81") (name "/D6_3V3") (class "Default")
      (node (ref "R55") (pin "1") (pinfunction "1_1") (pintype "passive"))
      (node (ref "R56") (pin "2") (pinfunction "2_2") (pintype "passive"))
      (node (ref "U8") (pin "10") (pinfunction "3IN+_10") (pintype "input"))
    )
    (net (code "82") (name "/D6_BUFFERED") (class "Default")
      (node (ref "U7") (pin "12") (pinfunction "GIOA[6]/INT[6]_12") (pintype "bidirectional"))
      (node (ref "U8") (pin "8") (pinfunction "3OUT_8") (pintype "output"))
      (node (ref "U8") (pin "9") (pinfunction "3IN-_9") (pintype "input"))
    )
    (net (code "83") (name "/D6_IN") (class "Default")
      (node (ref "D24") (pin "2") (pinfunction "2_2") (pintype "passive"))
      (node (ref "R77") (pin "2") (pinfunction "2_2") (pintype "passive"))
      (node (ref "X1") (pin "29") (pinfunction "1_29") (pintype "passive"))
    )
    (net (code "84") (name "/D7_3V3") (class "Default")
      (node (ref "R57") (pin "1") (pinfunction "1_1") (pintype "passive"))
      (node (ref "R58") (pin "2") (pinfunction "2_2") (pintype "passive"))
      (node (ref "U8") (pin "12") (pinfunction "4IN+_12") (pintype "input"))
    )
    (net (code "85") (name "/D7_BUFFERED") (class "Default")
      (node (ref "U7") (pin "18") (pinfunction "GIOA[7]/INT[7]_18") (pintype "bidirectional"))
      (node (ref "U8") (pin "13") (pinfunction "4IN-_13") (pintype "input"))
      (node (ref "U8") (pin "14") (pinfunction "4OUT_14") (pintype "output"))
    )
    (net (code "86") (name "/D7_IN") (class "Default")
      (node (ref "D35") (pin "2") (pinfunction "2_2") (pintype "passive"))
      (node (ref "R78") (pin "2") (pinfunction "2_2") (pintype "passive"))
      (node (ref "X1") (pin "30") (pinfunction "1_30") (pintype "passive"))
    )
    (net (code "87") (name "/DM") (class "Default")
      (node (ref "R41") (pin "2") (pinfunction "2_2") (pintype "passive"))
      (node (ref "U10") (pin "7") (pinfunction "DM_7") (pintype "bidirectional"))
    )
    (net (code "88") (name "/DP") (class "Default")
      (node (ref "R42") (pin "2") (pinfunction "2_2") (pintype "passive"))
      (node (ref "U10") (pin "8") (pinfunction "DP_8") (pintype "bidirectional"))
    )
    (net (code "89") (name "/FTDI_TCK") (class "Default")
      (node (ref "U10") (pin "16") (pinfunction "ADBUS0_16") (pintype "bidirectional"))
      (node (ref "U9") (pin "H10") (pinfunction "IO12_14_H10") (pintype "bidirectional"))
    )
    (net (code "90") (name "/FTDI_TDI") (class "Default")
      (node (ref "Q1") (pin "3") (pinfunction "G_3") (pintype "passive"))
      (node (ref "R115") (pin "1") (pinfunction "1_1") (pintype "passive"))
      (node (ref "U10") (pin "17") (pinfunction "ADBUS1_17") (pintype "bidirectional"))
      (node (ref "U9") (pin "K8") (pinfunction "IO12_13_K8") (pintype "bidirectional"))
    )
    (net (code "91") (name "/FTDI_TDO") (class "Default")
      (node (ref "U10") (pin "18") (pinfunction "ADBUS2_18") (pintype "bidirectional"))
      (node (ref "U9") (pin "H8") (pinfunction "IO12_12_H8") (pintype "bidirectional"))
    )
    (net (code "92") (name "/FTDI_TMS") (class "Default")
      (node (ref "U10") (pin "19") (pinfunction "ADBUS3_19") (pintype "bidirectional"))
      (node (ref "U9") (pin "H5") (pinfunction "IO12_11_H5") (pintype "bidirectional"))
    )
    (net (code "93") (name "/GPIOH0") (class "Default")
      (node (ref "U10") (pin "26") (pinfunction "ACBUS0_26") (pintype "bidirectional"))
      (node (ref "U9") (pin "K1") (pinfunction "IO12_6_K1") (pintype "bidirectional"))
    )
    (net (code "94") (name "/GPIOH1") (class "Default")
      (node (ref "U10") (pin "27") (pinfunction "ACBUS1_27") (pintype "bidirectional"))
      (node (ref "U9") (pin "J1") (pinfunction "IO12_5_J1") (pintype "bidirectional"))
    )
    (net (code "95") (name "/GPIOH3") (class "Default")
      (node (ref "U10") (pin "29") (pinfunction "ACBUS3_29") (pintype "bidirectional"))
      (node (ref "U9") (pin "F3") (pinfunction "IO12_2_F3") (pintype "bidirectional"))
    )
    (net (code "96") (name "/GPIOL0") (class "Default")
      (node (ref "U10") (pin "21") (pinfunction "ADBUS4_21") (pintype "bidirectional"))
      (node (ref "U9") (pin "K5") (pinfunction "IO12_10_K5") (pintype "bidirectional"))
    )
    (net (code "97") (name "/GPIOL1") (class "Default")
      (node (ref "U10") (pin "22") (pinfunction "ADBUS5_22") (pintype "bidirectional"))
      (node (ref "U9") (pin "H3") (pinfunction "IO12_9_H3") (pintype "bidirectional"))
    )
    (net (code "98") (name "/GPIOL2") (class "Default")
      (node (ref "U10") (pin "23") (pinfunction "ADBUS6_23") (pintype "bidirectional"))
      (node (ref "U9") (pin "K3") (pinfunction "IO12_8_K3") (pintype "bidirectional"))
    )
    (net (code "99") (name "/GPIOL3") (class "Default")
      (node (ref "U10") (pin "24") (pinfunction "ADBUS7_24") (pintype "bidirectional"))
      (node (ref "U9") (pin "K2") (pinfunction "IO12_7_K2") (pintype "bidirectional"))
    )
    (net (code "100") (name "/JTAG_SEL") (class "Default")
      (node (ref "C75") (pin "1") (pinfunction "1_1") (pintype "passive"))
      (node (ref "Q3") (pin "3") (pinfunction "G_3") (pintype "passive"))
      (node (ref "R60") (pin "1") (pinfunction "1_1") (pintype "passive"))
    )
    (net (code "101") (name "/MCU_RESET") (class "Default")
      (node (ref "R89") (pin "1") (pinfunction "1_1") (pintype "passive"))
      (node (ref "U7") (pin "81") (pinfunction "NRST_81") (pintype "bidirectional"))
    )
    (net (code "102") (name "/MCU_RTCK") (class "Default")
      (node (ref "R86") (pin "2") (pinfunction "2_2") (pintype "passive"))
      (node (ref "U7") (pin "80") (pinfunction "RTCK_80") (pintype "bidirectional"))
    )
    (net (code "103") (name "/MCU_TCK") (class "Default")
      (node (ref "R90") (pin "1") (pinfunction "1_1") (pintype "passive"))
      (node (ref "U7") (pin "79") (pinfunction "TCK_79") (pintype "bidirectional"))
    )
    (net (code "104") (name "/MCU_TDI") (class "Default")
      (node (ref "R93") (pin "1") (pinfunction "1_1") (pintype "passive"))
      (node (ref "U7") (pin "77") (pinfunction "TDI_77") (pintype "bidirectional"))
    )
    (net (code "105") (name "/MCU_TDO") (class "Default")
      (node (ref "R91") (pin "1") (pinfunction "1_1") (pintype "passive"))
      (node (ref "U7") (pin "78") (pinfunction "TDO_78") (pintype "bidirectional"))
    )
    (net (code "106") (name "/MCU_TMS") (class "Default")
      (node (ref "R95") (pin "1") (pinfunction "1_1") (pintype "passive"))
      (node (ref "U7") (pin "75") (pinfunction "TMS_75") (pintype "bidirectional"))
    )
    (net (code "107") (name "/MCU_TRSTN") (class "Default")
      (node (ref "R94") (pin "1") (pinfunction "1_1") (pintype "passive"))
      (node (ref "U7") (pin "76") (pinfunction "NTRST_76") (pintype "bidirectional"))
    )
    (net (code "108") (name "/N$13") (class "Default")
      (node (ref "D36") (pin "2") (pinfunction "A_2") (pintype "passive"))
      (node (ref "TP1") (pin "TP") (pinfunction "PP_TP") (pintype "input"))
    )
    (net (code "109") (name "/POWERGOOD") (class "Default")
      (node (ref "C51") (pin "1") (pinfunction "1_1") (pintype "passive"))
      (node (ref "R97") (pin "1") (pinfunction "1_1") (pintype "passive"))
      (node (ref "U9") (pin "F10") (pinfunction "IO12_16_F10") (pintype "bidirectional"))
    )
    (net (code "110") (name "/POWER_EN") (class "Default")
      (node (ref "D26") (pin "C") (pinfunction "C_C") (pintype "passive"))
      (node (ref "U10") (pin "60") (pinfunction "PWREN_60") (pintype "bidirectional"))
      (node (ref "U9") (pin "G3") (pinfunction "IO12_4_G3") (pintype "bidirectional"))
    )
    (net (code "111") (name "/PWR_DET") (class "Default")
      (node (ref "U10") (pin "28") (pinfunction "ACBUS2_28") (pintype "bidirectional"))
      (node (ref "U9") (pin "H1") (pinfunction "IO12_3_H1") (pintype "bidirectional"))
    )
    (net (code "112") (name "/SCI1_RX") (class "Default")
      (node (ref "R103") (pin "2") (pinfunction "2_2") (pintype "passive"))
      (node (ref "U7") (pin "94") (pinfunction "LINRX_94") (pintype "bidirectional"))
    )
    (net (code "113") (name "/SCI1_TX") (class "Default")
      (node (ref "R104") (pin "2") (pinfunction "2_2") (pintype "passive"))
      (node (ref "U7") (pin "95") (pinfunction "LINTX_95") (pintype "bidirectional"))
    )
    (net (code "114") (name "/SPARE0") (class "Default")
      (node (ref "R98") (pin "2") (pinfunction "2_2") (pintype "passive"))
      (node (ref "U10") (pin "30") (pinfunction "ACBUS4_30") (pintype "bidirectional"))
      (node (ref "U9") (pin "F1") (pinfunction "IO21_1_F1") (pintype "bidirectional"))
    )
    (net (code "115") (name "/SPARE1") (class "Default")
      (node (ref "R99") (pin "2") (pinfunction "2_2") (pintype "passive"))
      (node (ref "U10") (pin "32") (pinfunction "ACBUS5_32") (pintype "bidirectional"))
      (node (ref "U9") (pin "E3") (pinfunction "IO21_2_E3") (pintype "bidirectional"))
    )
    (net (code "116") (name "/SPARE2") (class "Default")
      (node (ref "R100") (pin "2") (pinfunction "2_2") (pintype "passive"))
      (node (ref "U10") (pin "33") (pinfunction "ACBUS6_33") (pintype "bidirectional"))
      (node (ref "U9") (pin "E1") (pinfunction "IO21_3_E1") (pintype "bidirectional"))
    )
    (net (code "117") (name "/SPARE3") (class "Default")
      (node (ref "R101") (pin "2") (pinfunction "2_2") (pintype "passive"))
      (node (ref "U10") (pin "34") (pinfunction "ACBUS7_34") (pintype "bidirectional"))
      (node (ref "U9") (pin "D1") (pinfunction "IO21_4_D1") (pintype "bidirectional"))
    )
    (net (code "118") (name "/SUSPEED") (class "Default")
      (node (ref "U10") (pin "36") (pinfunction "SUSPEED_36") (pintype "bidirectional"))
      (node (ref "U9") (pin "G1") (pinfunction "IO12_1_G1") (pintype "bidirectional"))
    )
    (net (code "119") (name "/T_DIS") (class "Default")
      (node (ref "Q3") (pin "1") (pinfunction "D_1") (pintype "passive"))
      (node (ref "R102") (pin "2") (pinfunction "2_2") (pintype "passive"))
      (node (ref "R92") (pin "1") (pinfunction "1_1") (pintype "passive"))
    )
    (net (code "120") (name "GND") (class "Default")
      (node (ref "C1") (pin "2") (pinfunction "2_2") (pintype "passive"))
      (node (ref "C10") (pin "2") (pinfunction "2_2") (pintype "passive"))
      (node (ref "C11") (pin "2") (pinfunction "2_2") (pintype "passive"))
      (node (ref "C12") (pin "2") (pinfunction "2_2") (pintype "passive"))
      (node (ref "C13") (pin "2") (pinfunction "2_2") (pintype "passive"))
      (node (ref "C14") (pin "2") (pinfunction "2_2") (pintype "passive"))
      (node (ref "C15") (pin "2") (pinfunction "2_2") (pintype "passive"))
      (node (ref "C16") (pin "2") (pinfunction "2_2") (pintype "passive"))
      (node (ref "C17") (pin "2") (pinfunction "2_2") (pintype "passive"))
      (node (ref "C18") (pin "2") (pinfunction "2_2") (pintype "passive"))
      (node (ref "C19") (pin "2") (pinfunction "2_2") (pintype "passive"))
      (node (ref "C2") (pin "2") (pinfunction "2_2") (pintype "passive"))
      (node (ref "C20") (pin "2") (pinfunction "2_2") (pintype "passive"))
      (node (ref "C21") (pin "2") (pinfunction "2_2") (pintype "passive"))
      (node (ref "C22") (pin "2") (pinfunction "2_2") (pintype "passive"))
      (node (ref "C23") (pin "2") (pinfunction "2_2") (pintype "passive"))
      (node (ref "C24") (pin "2") (pinfunction "2_2") (pintype "passive"))
      (node (ref "C25") (pin "2") (pinfunction "2_2") (pintype "passive"))
      (node (ref "C26") (pin "2") (pinfunction "2_2") (pintype "passive"))
      (node (ref "C29") (pin "2") (pinfunction "2_2") (pintype "passive"))
      (node (ref "C3") (pin "+") (pinfunction "-_+") (pintype "passive"))
      (node (ref "C30") (pin "2") (pinfunction "2_2") (pintype "passive"))
      (node (ref "C31") (pin "2") (pinfunction "2_2") (pintype "passive"))
      (node (ref "C32") (pin "2") (pinfunction "2_2") (pintype "passive"))
      (node (ref "C33") (pin "2") (pinfunction "2_2") (pintype "passive"))
      (node (ref "C34") (pin "2") (pinfunction "2_2") (pintype "passive"))
      (node (ref "C35") (pin "2") (pinfunction "2_2") (pintype "passive"))
      (node (ref "C36") (pin "2") (pinfunction "2_2") (pintype "passive"))
      (node (ref "C37") (pin "2") (pinfunction "2_2") (pintype "passive"))
      (node (ref "C38") (pin "2") (pinfunction "2_2") (pintype "passive"))
      (node (ref "C39") (pin "2") (pinfunction "2_2") (pintype "passive"))
      (node (ref "C4") (pin "+") (pinfunction "-_+") (pintype "passive"))
      (node (ref "C40") (pin "2") (pinfunction "2_2") (pintype "passive"))
      (node (ref "C41") (pin "2") (pinfunction "2_2") (pintype "passive"))
      (node (ref "C42") (pin "2") (pinfunction "2_2") (pintype "passive"))
      (node (ref "C43") (pin "2") (pinfunction "2_2") (pintype "passive"))
      (node (ref "C44") (pin "2") (pinfunction "2_2") (pintype "passive"))
      (node (ref "C45") (pin "2") (pinfunction "2_2") (pintype "passive"))
      (node (ref "C46") (pin "2") (pinfunction "2_2") (pintype "passive"))
      (node (ref "C47") (pin "2") (pinfunction "2_2") (pintype "passive"))
      (node (ref "C48") (pin "2") (pinfunction "2_2") (pintype "passive"))
      (node (ref "C49") (pin "2") (pinfunction "2_2") (pintype "passive"))
      (node (ref "C5") (pin "+") (pinfunction "-_+") (pintype "passive"))
      (node (ref "C50") (pin "2") (pinfunction "2_2") (pintype "passive"))
      (node (ref "C51") (pin "2") (pinfunction "2_2") (pintype "passive"))
      (node (ref "C52") (pin "2") (pinfunction "2_2") (pintype "passive"))
      (node (ref "C53") (pin "2") (pinfunction "2_2") (pintype "passive"))
      (node (ref "C54") (pin "2") (pinfunction "2_2") (pintype "passive"))
      (node (ref "C55") (pin "2") (pinfunction "2_2") (pintype "passive"))
      (node (ref "C56") (pin "2") (pinfunction "2_2") (pintype "passive"))
      (node (ref "C57") (pin "2") (pinfunction "2_2") (pintype "passive"))
      (node (ref "C58") (pin "2") (pinfunction "2_2") (pintype "passive"))
      (node (ref "C59") (pin "2") (pinfunction "2_2") (pintype "passive"))
      (node (ref "C6") (pin "2") (pinfunction "2_2") (pintype "passive"))
      (node (ref "C60") (pin "2") (pinfunction "2_2") (pintype "passive"))
      (node (ref "C61") (pin "2") (pinfunction "2_2") (pintype "passive"))
      (node (ref "C62") (pin "2") (pinfunction "2_2") (pintype "passive"))
      (node (ref "C63") (pin "2") (pinfunction "2_2") (pintype "passive"))
      (node (ref "C64") (pin "2") (pinfunction "2_2") (pintype "passive"))
      (node (ref "C65") (pin "2") (pinfunction "2_2") (pintype "passive"))
      (node (ref "C66") (pin "2") (pinfunction "2_2") (pintype "passive"))
      (node (ref "C67") (pin "2") (pinfunction "2_2") (pintype "passive"))
      (node (ref "C68") (pin "2") (pinfunction "2_2") (pintype "passive"))
      (node (ref "C69") (pin "2") (pinfunction "2_2") (pintype "passive"))
      (node (ref "C7") (pin "2") (pinfunction "2_2") (pintype "passive"))
      (node (ref "C70") (pin "2") (pinfunction "2_2") (pintype "passive"))
      (node (ref "C71") (pin "2") (pinfunction "2_2") (pintype "passive"))
      (node (ref "C72") (pin "2") (pinfunction "2_2") (pintype "passive"))
      (node (ref "C73") (pin "2") (pinfunction "2_2") (pintype "passive"))
      (node (ref "C74") (pin "2") (pinfunction "2_2") (pintype "passive"))
      (node (ref "C75") (pin "2") (pinfunction "2_2") (pintype "passive"))
      (node (ref "C76") (pin "2") (pinfunction "2_2") (pintype "passive"))
      (node (ref "C8") (pin "2") (pinfunction "2_2") (pintype "passive"))
      (node (ref "C9") (pin "2") (pinfunction "2_2") (pintype "passive"))
      (node (ref "D1") (pin "2") (pinfunction "2_2") (pintype "passive"))
      (node (ref "D10") (pin "1") (pinfunction "1_1") (pintype "passive"))
      (node (ref "D11") (pin "1") (pinfunction "1_1") (pintype "passive"))
      (node (ref "D12") (pin "1") (pinfunction "1_1") (pintype "passive"))
      (node (ref "D13") (pin "1") (pinfunction "1_1") (pintype "passive"))
      (node (ref "D14") (pin "1") (pinfunction "1_1") (pintype "passive"))
      (node (ref "D15") (pin "1") (pinfunction "1_1") (pintype "passive"))
      (node (ref "D16") (pin "1") (pinfunction "1_1") (pintype "passive"))
      (node (ref "D17") (pin "1") (pinfunction "1_1") (pintype "passive"))
      (node (ref "D18") (pin "1") (pinfunction "1_1") (pintype "passive"))
      (node (ref "D19") (pin "1") (pinfunction "1_1") (pintype "passive"))
      (node (ref "D2") (pin "1") (pinfunction "1_1") (pintype "passive"))
      (node (ref "D20") (pin "1") (pinfunction "1_1") (pintype "passive"))
      (node (ref "D21") (pin "1") (pinfunction "1_1") (pintype "passive"))
      (node (ref "D22") (pin "1") (pinfunction "1_1") (pintype "passive"))
      (node (ref "D23") (pin "1") (pinfunction "1_1") (pintype "passive"))
      (node (ref "D24") (pin "1") (pinfunction "1_1") (pintype "passive"))
      (node (ref "D25") (pin "2") (pinfunction "2_2") (pintype "passive"))
      (node (ref "D29") (pin "C") (pinfunction "C_C") (pintype "passive"))
      (node (ref "D3") (pin "1") (pinfunction "1_1") (pintype "passive"))
      (node (ref "D30") (pin "1") (pinfunction "1_1") (pintype "passive"))
      (node (ref "D31") (pin "1") (pinfunction "1_1") (pintype "passive"))
      (node (ref "D32") (pin "1") (pinfunction "1_1") (pintype "passive"))
      (node (ref "D33") (pin "1") (pinfunction "1_1") (pintype "passive"))
      (node (ref "D34") (pin "1") (pinfunction "1_1") (pintype "passive"))
      (node (ref "D35") (pin "1") (pinfunction "1_1") (pintype "passive"))
      (node (ref "D37") (pin "1") (pinfunction "1_1") (pintype "passive"))
      (node (ref "D38") (pin "C@1") (pinfunction "C_C@1") (pintype "passive"))
      (node (ref "D4") (pin "1") (pinfunction "1_1") (pintype "passive"))
      (node (ref "D5") (pin "1") (pinfunction "1_1") (pintype "passive"))
      (node (ref "D6") (pin "1") (pinfunction "1_1") (pintype "passive"))
      (node (ref "D7") (pin "1") (pinfunction "1_1") (pintype "passive"))
      (node (ref "D8") (pin "2") (pinfunction "2_2") (pintype "passive"))
      (node (ref "D9") (pin "1") (pinfunction "1_1") (pintype "passive"))
      (node (ref "IC1") (pin "4") (pinfunction "GND1_4") (pintype "input"))
      (node (ref "IC1") (pin "5") (pinfunction "GND2_5") (pintype "input"))
      (node (ref "IC2") (pin "4") (pinfunction "GND1_4") (pintype "input"))
      (node (ref "IC2") (pin "5") (pinfunction "GND2_5") (pintype "input"))
      (node (ref "R102") (pin "1") (pinfunction "1_1") (pintype "passive"))
      (node (ref "R11") (pin "1") (pinfunction "1_1") (pintype "passive"))
      (node (ref "R110") (pin "1") (pinfunction "1_1") (pintype "passive"))
      (node (ref "R13") (pin "1") (pinfunction "1_1") (pintype "passive"))
      (node (ref "R15") (pin "1") (pinfunction "1_1") (pintype "passive"))
      (node (ref "R17") (pin "1") (pinfunction "1_1") (pintype "passive"))
      (node (ref "R19") (pin "1") (pinfunction "1_1") (pintype "passive"))
      (node (ref "R21") (pin "1") (pinfunction "1_1") (pintype "passive"))
      (node (ref "R23") (pin "1") (pinfunction "1_1") (pintype "passive"))
      (node (ref "R25") (pin "1") (pinfunction "1_1") (pintype "passive"))
      (node (ref "R27") (pin "1") (pinfunction "1_1") (pintype "passive"))
      (node (ref "R29") (pin "1") (pinfunction "1_1") (pintype "passive"))
      (node (ref "R31") (pin "1") (pinfunction "1_1") (pintype "passive"))
      (node (ref "R33") (pin "1") (pinfunction "1_1") (pintype "passive"))
      (node (ref "R35") (pin "1") (pinfunction "1_1") (pintype "passive"))
      (node (ref "R37") (pin "1") (pinfunction "1_1") (pintype "passive"))
      (node (ref "R39") (pin "1") (pinfunction "1_1") (pintype "passive"))
      (node (ref "R44") (pin "1") (pinfunction "1_1") (pintype "passive"))
      (node (ref "R46") (pin "1") (pinfunction "1_1") (pintype "passive"))
      (node (ref "R48") (pin "1") (pinfunction "1_1") (pintype "passive"))
      (node (ref "R50") (pin "1") (pinfunction "1_1") (pintype "passive"))
      (node (ref "R52") (pin "1") (pinfunction "1_1") (pintype "passive"))
      (node (ref "R54") (pin "1") (pinfunction "1_1") (pintype "passive"))
      (node (ref "R56") (pin "1") (pinfunction "1_1") (pintype "passive"))
      (node (ref "R58") (pin "1") (pinfunction "1_1") (pintype "passive"))
      (node (ref "R59") (pin "1") (pinfunction "1_1") (pintype "passive"))
      (node (ref "R9") (pin "1") (pinfunction "1_1") (pintype "passive"))
      (node (ref "U$5") (pin "5") (pinfunction "GND_5") (pintype "power_in"))
      (node (ref "U1") (pin "11") (pinfunction "GND_11") (pintype "passive"))
      (node (ref "U10") (pin "1") (pinfunction "GND1_1") (pintype "bidirectional"))
      (node (ref "U10") (pin "10") (pinfunction "GNDA_10") (pintype "bidirectional"))
      (node (ref "U10") (pin "11") (pinfunction "GND3_11") (pintype "bidirectional"))
      (node (ref "U10") (pin "13") (pinfunction "TEST_13") (pintype "bidirectional"))
      (node (ref "U10") (pin "15") (pinfunction "GND4_15") (pintype "bidirectional"))
      (node (ref "U10") (pin "25") (pinfunction "GND5_25") (pintype "bidirectional"))
      (node (ref "U10") (pin "35") (pinfunction "GND6_35") (pintype "bidirectional"))
      (node (ref "U10") (pin "47") (pinfunction "GND7_47") (pintype "bidirectional"))
      (node (ref "U10") (pin "5") (pinfunction "GND2_5") (pintype "bidirectional"))
      (node (ref "U10") (pin "51") (pinfunction "GND8_51") (pintype "bidirectional"))
      (node (ref "U11") (pin "5") (pinfunction "GND_5") (pintype "bidirectional"))
      (node (ref "U2") (pin "1") (pinfunction "GND/HEATSINK_2_1") (pintype "power_in"))
      (node (ref "U2") (pin "12") (pinfunction "GND/HEATSINK_4_12") (pintype "power_in"))
      (node (ref "U2") (pin "13") (pinfunction "GND/HEATSINK_5_13") (pintype "power_in"))
      (node (ref "U2") (pin "24") (pinfunction "GND/HEATSINK_24") (pintype "power_in"))
      (node (ref "U2") (pin "6") (pinfunction "*EN1_6") (pintype "input"))
      (node (ref "U2") (pin "7") (pinfunction "*EN2_7") (pintype "input"))
      (node (ref "U2") (pin "9") (pinfunction "GND/HEATSINK_3_9") (pintype "power_in"))
      (node (ref "U2") (pin "EPAD") (pinfunction "EPAD_EPAD") (pintype "passive"))
      (node (ref "U3") (pin "11") (pinfunction "GND_11") (pintype "passive"))
      (node (ref "U4") (pin "11") (pinfunction "GND_11") (pintype "passive"))
      (node (ref "U5") (pin "11") (pinfunction "GND_11") (pintype "passive"))
      (node (ref "U6") (pin "11") (pinfunction "GND_11") (pintype "passive"))
      (node (ref "U7") (pin "100") (pinfunction "VSS_100") (pintype "power_in"))
      (node (ref "U7") (pin "17") (pinfunction "VSS_3_17") (pintype "power_in"))
      (node (ref "U7") (pin "20") (pinfunction "VSS_4_20") (pintype "power_in"))
      (node (ref "U7") (pin "29") (pinfunction "VSS_5_29") (pintype "power_in"))
      (node (ref "U7") (pin "33") (pinfunction "VSS_6_33") (pintype "power_in"))
      (node (ref "U7") (pin "47") (pinfunction "VSSAD/ADREFLO_47") (pintype "bidirectional"))
      (node (ref "U7") (pin "59") (pinfunction "VSS_7_59") (pintype "power_in"))
      (node (ref "U7") (pin "7") (pinfunction "VSS_2_7") (pintype "power_in"))
      (node (ref "U7") (pin "72") (pinfunction "VSS_8_72") (pintype "power_in"))
      (node (ref "U7") (pin "86") (pinfunction "VSS_9_86") (pintype "power_in"))
      (node (ref "U7") (pin "87") (pinfunction "VSS_10_87") (pintype "power_in"))
      (node (ref "U8") (pin "11") (pinfunction "GND_11") (pintype "passive"))
      (node (ref "U9") (pin "C7") (pinfunction "GND3_C7") (pintype "bidirectional"))
      (node (ref "U9") (pin "F8") (pinfunction "GND2_F8") (pintype "bidirectional"))
      (node (ref "U9") (pin "H4") (pinfunction "GND1_H4") (pintype "bidirectional"))
      (node (ref "X1") (pin "2") (pinfunction "1_2") (pintype "passive"))
      (node (ref "X2") (pin "2") (pinfunction "K_2") (pintype "passive"))
      (node (ref "Y1") (pin "P$2") (pinfunction "P$2_P$2") (pintype "bidirectional"))
      (node (ref "Y1") (pin "P$4") (pinfunction "P$4_P$4") (pintype "bidirectional"))
    )
    (net (code "121") (name "Net-(C8-Pad1)") (class "Default")
      (node (ref "C8") (pin "1") (pinfunction "1_1") (pintype "passive"))
      (node (ref "R51") (pin "2") (pinfunction "2_2") (pintype "passive"))
      (node (ref "R68") (pin "1") (pinfunction "1_1") (pintype "passive"))
    )
    (net (code "122") (name "Net-(C11-Pad1)") (class "Default")
      (node (ref "C11") (pin "1") (pinfunction "1_1") (pintype "passive"))
      (node (ref "R12") (pin "2") (pinfunction "2_2") (pintype "passive"))
      (node (ref "R61") (pin "1") (pinfunction "1_1") (pintype "passive"))
    )
    (net (code "123") (name "Net-(C12-Pad1)") (class "Default")
      (node (ref "C12") (pin "1") (pinfunction "1_1") (pintype "passive"))
      (node (ref "R62") (pin "1") (pinfunction "1_1") (pintype "passive"))
      (node (ref "R8") (pin "2") (pinfunction "2_2") (pintype "passive"))
    )
    (net (code "124") (name "Net-(C29-Pad1)") (class "Default")
      (node (ref "C29") (pin "1") (pinfunction "1_1") (pintype "passive"))
      (node (ref "R16") (pin "2") (pinfunction "2_2") (pintype "passive"))
      (node (ref "R63") (pin "1") (pinfunction "1_1") (pintype "passive"))
    )
    (net (code "125") (name "Net-(C30-Pad1)") (class "Default")
      (node (ref "C30") (pin "1") (pinfunction "1_1") (pintype "passive"))
      (node (ref "R24") (pin "2") (pinfunction "2_2") (pintype "passive"))
      (node (ref "R64") (pin "1") (pinfunction "1_1") (pintype "passive"))
    )
    (net (code "126") (name "Net-(C31-Pad1)") (class "Default")
      (node (ref "C31") (pin "1") (pinfunction "1_1") (pintype "passive"))
      (node (ref "R32") (pin "2") (pinfunction "2_2") (pintype "passive"))
      (node (ref "R65") (pin "1") (pinfunction "1_1") (pintype "passive"))
    )
    (net (code "127") (name "Net-(C32-Pad1)") (class "Default")
      (node (ref "C32") (pin "1") (pinfunction "1_1") (pintype "passive"))
      (node (ref "R43") (pin "2") (pinfunction "2_2") (pintype "passive"))
      (node (ref "R66") (pin "1") (pinfunction "1_1") (pintype "passive"))
    )
    (net (code "128") (name "Net-(C33-Pad1)") (class "Default")
      (node (ref "C33") (pin "1") (pinfunction "1_1") (pintype "passive"))
      (node (ref "R53") (pin "2") (pinfunction "2_2") (pintype "passive"))
      (node (ref "R69") (pin "1") (pinfunction "1_1") (pintype "passive"))
    )
    (net (code "129") (name "Net-(C34-Pad1)") (class "Default")
      (node (ref "C34") (pin "1") (pinfunction "1_1") (pintype "passive"))
      (node (ref "R47") (pin "2") (pinfunction "2_2") (pintype "passive"))
      (node (ref "R67") (pin "1") (pinfunction "1_1") (pintype "passive"))
    )
    (net (code "130") (name "Net-(C35-Pad1)") (class "Default")
      (node (ref "C35") (pin "1") (pinfunction "1_1") (pintype "passive"))
      (node (ref "R40") (pin "1") (pinfunction "1_1") (pintype "passive"))
      (node (ref "R45") (pin "2") (pinfunction "2_2") (pintype "passive"))
    )
    (net (code "131") (name "Net-(C36-Pad1)") (class "Default")
      (node (ref "C36") (pin "1") (pinfunction "1_1") (pintype "passive"))
      (node (ref "R34") (pin "2") (pinfunction "2_2") (pintype "passive"))
      (node (ref "R70") (pin "1") (pinfunction "1_1") (pintype "passive"))
    )
    (net (code "132") (name "Net-(C37-Pad1)") (class "Default")
      (node (ref "C37") (pin "1") (pinfunction "1_1") (pintype "passive"))
      (node (ref "R26") (pin "2") (pinfunction "2_2") (pintype "passive"))
      (node (ref "R71") (pin "1") (pinfunction "1_1") (pintype "passive"))
    )
    (net (code "133") (name "Net-(C38-Pad1)") (class "Default")
      (node (ref "C38") (pin "1") (pinfunction "1_1") (pintype "passive"))
      (node (ref "R18") (pin "2") (pinfunction "2_2") (pintype "passive"))
      (node (ref "R72") (pin "1") (pinfunction "1_1") (pintype "passive"))
    )
    (net (code "134") (name "Net-(C39-Pad1)") (class "Default")
      (node (ref "C39") (pin "1") (pinfunction "1_1") (pintype "passive"))
      (node (ref "R10") (pin "2") (pinfunction "2_2") (pintype "passive"))
      (node (ref "R73") (pin "1") (pinfunction "1_1") (pintype "passive"))
    )
    (net (code "135") (name "Net-(C40-Pad1)") (class "Default")
      (node (ref "C40") (pin "1") (pinfunction "1_1") (pintype "passive"))
      (node (ref "R20") (pin "2") (pinfunction "2_2") (pintype "passive"))
      (node (ref "R74") (pin "1") (pinfunction "1_1") (pintype "passive"))
    )
    (net (code "136") (name "Net-(C41-Pad1)") (class "Default")
      (node (ref "C41") (pin "1") (pinfunction "1_1") (pintype "passive"))
      (node (ref "R28") (pin "2") (pinfunction "2_2") (pintype "passive"))
      (node (ref "R75") (pin "1") (pinfunction "1_1") (pintype "passive"))
    )
    (net (code "137") (name "Net-(C42-Pad1)") (class "Default")
      (node (ref "C42") (pin "1") (pinfunction "1_1") (pintype "passive"))
      (node (ref "R36") (pin "2") (pinfunction "2_2") (pintype "passive"))
      (node (ref "R76") (pin "1") (pinfunction "1_1") (pintype "passive"))
    )
    (net (code "138") (name "Net-(C43-Pad1)") (class "Default")
      (node (ref "C43") (pin "1") (pinfunction "1_1") (pintype "passive"))
      (node (ref "R55") (pin "2") (pinfunction "2_2") (pintype "passive"))
      (node (ref "R77") (pin "1") (pinfunction "1_1") (pintype "passive"))
    )
    (net (code "139") (name "Net-(C44-Pad1)") (class "Default")
      (node (ref "C44") (pin "1") (pinfunction "1_1") (pintype "passive"))
      (node (ref "R57") (pin "2") (pinfunction "2_2") (pintype "passive"))
      (node (ref "R78") (pin "1") (pinfunction "1_1") (pintype "passive"))
    )
    (net (code "140") (name "Net-(C45-Pad1)") (class "Default")
      (node (ref "C45") (pin "1") (pinfunction "1_1") (pintype "passive"))
      (node (ref "R49") (pin "2") (pinfunction "2_2") (pintype "passive"))
      (node (ref "R79") (pin "1") (pinfunction "1_1") (pintype "passive"))
    )
    (net (code "141") (name "Net-(C47-Pad1)") (class "Default")
      (node (ref "C47") (pin "1") (pinfunction "1_1") (pintype "passive"))
      (node (ref "R38") (pin "2") (pinfunction "2_2") (pintype "passive"))
      (node (ref "R81") (pin "1") (pinfunction "1_1") (pintype "passive"))
    )
    (net (code "142") (name "Net-(C48-Pad1)") (class "Default")
      (node (ref "C48") (pin "1") (pinfunction "1_1") (pintype "passive"))
      (node (ref "R30") (pin "2") (pinfunction "2_2") (pintype "passive"))
      (node (ref "R82") (pin "1") (pinfunction "1_1") (pintype "passive"))
    )
    (net (code "143") (name "Net-(C49-Pad1)") (class "Default")
      (node (ref "C49") (pin "1") (pinfunction "1_1") (pintype "passive"))
      (node (ref "R22") (pin "2") (pinfunction "2_2") (pintype "passive"))
      (node (ref "R83") (pin "1") (pinfunction "1_1") (pintype "passive"))
    )
    (net (code "144") (name "Net-(C50-Pad1)") (class "Default")
      (node (ref "C50") (pin "1") (pinfunction "1_1") (pintype "passive"))
      (node (ref "R14") (pin "2") (pinfunction "2_2") (pintype "passive"))
      (node (ref "R84") (pin "1") (pinfunction "1_1") (pintype "passive"))
    )
    (net (code "145") (name "Net-(D26-PadA)") (class "Default")
      (node (ref "D26") (pin "A") (pinfunction "A_A") (pintype "passive"))
      (node (ref "R96") (pin "2") (pinfunction "2_2") (pintype "passive"))
    )
    (net (code "146") (name "Net-(D27-PadC)") (class "Default")
      (node (ref "D27") (pin "C") (pinfunction "C_C") (pintype "passive"))
      (node (ref "R106") (pin "2") (pinfunction "2_2") (pintype "passive"))
    )
    (net (code "147") (name "Net-(D28-PadC)") (class "Default")
      (node (ref "D28") (pin "C") (pinfunction "C_C") (pintype "passive"))
      (node (ref "R107") (pin "2") (pinfunction "2_2") (pintype "passive"))
    )
    (net (code "148") (name "Net-(D29-PadA)") (class "Default")
      (node (ref "D29") (pin "A") (pinfunction "A_A") (pintype "passive"))
      (node (ref "R114") (pin "1") (pinfunction "1_1") (pintype "passive"))
    )
    (net (code "149") (name "Net-(D36-C)") (class "Default")
      (node (ref "D36") (pin "1") (pinfunction "C_1") (pintype "passive"))
      (node (ref "R7") (pin "1") (pinfunction "1_1") (pintype "passive"))
      (node (ref "U2") (pin "8") (pinfunction "*RESET_8") (pintype "output"))
    )
    (net (code "150") (name "Net-(D38-A)") (class "Default")
      (node (ref "D38") (pin "A@1") (pinfunction "A_A@1") (pintype "passive"))
      (node (ref "R3") (pin "1") (pinfunction "1_1") (pintype "passive"))
    )
    (net (code "151") (name "Net-(IC1-RXD)") (class "Default")
      (node (ref "IC1") (pin "2") (pinfunction "RXD_2") (pintype "input"))
      (node (ref "U7") (pin "63") (pinfunction "CAN1RX_63") (pintype "bidirectional"))
    )
    (net (code "152") (name "Net-(IC1-TXD)") (class "Default")
      (node (ref "IC1") (pin "3") (pinfunction "TXD_3") (pintype "input"))
      (node (ref "U7") (pin "62") (pinfunction "CAN1TX_62") (pintype "bidirectional"))
    )
    (net (code "153") (name "Net-(IC2-RXD)") (class "Default")
      (node (ref "IC2") (pin "2") (pinfunction "RXD_2") (pintype "input"))
      (node (ref "U7") (pin "92") (pinfunction "CAN2RX_92") (pintype "bidirectional"))
    )
    (net (code "154") (name "Net-(IC2-TXD)") (class "Default")
      (node (ref "IC2") (pin "3") (pinfunction "TXD_3") (pintype "input"))
      (node (ref "U7") (pin "91") (pinfunction "CAN2TX_91") (pintype "bidirectional"))
    )
    (net (code "155") (name "Net-(Q1-D)") (class "Default")
      (node (ref "Q1") (pin "1") (pinfunction "D_1") (pintype "passive"))
      (node (ref "R114") (pin "2") (pinfunction "2_2") (pintype "passive"))
    )
    (net (code "156") (name "Net-(U$5-D+)") (class "Default")
      (node (ref "D3") (pin "2") (pinfunction "2_2") (pintype "passive"))
      (node (ref "R42") (pin "1") (pinfunction "1_1") (pintype "passive"))
      (node (ref "U$5") (pin "3") (pinfunction "D+_3") (pintype "bidirectional"))
    )
    (net (code "157") (name "Net-(U$5-D-)") (class "Default")
      (node (ref "D2") (pin "2") (pinfunction "2_2") (pintype "passive"))
      (node (ref "R41") (pin "1") (pinfunction "1_1") (pintype "passive"))
      (node (ref "U$5") (pin "2") (pinfunction "D-_2") (pintype "bidirectional"))
    )
    (net (code "158") (name "Net-(U2-*MR)") (class "Default")
      (node (ref "R1") (pin "1") (pinfunction "1_1") (pintype "passive"))
      (node (ref "R2") (pin "1") (pinfunction "1_1") (pintype "passive"))
      (node (ref "U2") (pin "18") (pinfunction "PG2_18") (pintype "output"))
      (node (ref "U2") (pin "19") (pinfunction "PG1_19") (pintype "output"))
      (node (ref "U2") (pin "5") (pinfunction "*MR_5") (pintype "input"))
    )
    (net (code "159") (name "Net-(U7-KELVIN_GND)") (class "Default")
      (node (ref "C27") (pin "2") (pinfunction "2_2") (pintype "passive"))
      (node (ref "C28") (pin "1") (pinfunction "1_1") (pintype "passive"))
      (node (ref "U7") (pin "15") (pinfunction "KELVIN_GND_15") (pintype "bidirectional"))
    )
    (net (code "160") (name "Net-(U7-OSCIN)") (class "Default")
      (node (ref "C27") (pin "1") (pinfunction "1_1") (pintype "passive"))
      (node (ref "U7") (pin "14") (pinfunction "OSCIN_14") (pintype "bidirectional"))
      (node (ref "XTAL1") (pin "1") (pinfunction "1_1") (pintype "passive"))
    )
    (net (code "161") (name "Net-(U7-OSCOUT)") (class "Default")
      (node (ref "C28") (pin "2") (pinfunction "2_2") (pintype "passive"))
      (node (ref "U7") (pin "16") (pinfunction "OSCOUT_16") (pintype "bidirectional"))
      (node (ref "XTAL1") (pin "3") (pinfunction "3_3") (pintype "passive"))
    )
    (net (code "162") (name "Net-(U9-I)") (class "Default")
      (node (ref "R86") (pin "1") (pinfunction "1_1") (pintype "passive"))
      (node (ref "U9") (pin "D10") (pinfunction "I_D10") (pintype "bidirectional"))
    )
    (net (code "163") (name "Net-(U9-IO21_5)") (class "Default")
      (node (ref "R95") (pin "2") (pinfunction "2_2") (pintype "passive"))
      (node (ref "U9") (pin "A3") (pinfunction "IO21_6_A3") (pintype "bidirectional"))
      (node (ref "U9") (pin "C1") (pinfunction "IO21_5_C1") (pintype "bidirectional"))
    )
    (net (code "164") (name "Net-(U9-IO21_7)") (class "Default")
      (node (ref "R94") (pin "2") (pinfunction "2_2") (pintype "passive"))
      (node (ref "U9") (pin "A2") (pinfunction "IO21_7_A2") (pintype "bidirectional"))
    )
    (net (code "165") (name "Net-(U9-IO21_8)") (class "Default")
      (node (ref "R93") (pin "2") (pinfunction "2_2") (pintype "passive"))
      (node (ref "U9") (pin "B1") (pinfunction "IO21_8_B1") (pintype "bidirectional"))
    )
    (net (code "166") (name "Net-(U9-IO21_9)") (class "Default")
      (node (ref "R92") (pin "2") (pinfunction "2_2") (pintype "passive"))
      (node (ref "U9") (pin "A1") (pinfunction "IO21_9_A1") (pintype "bidirectional"))
    )
    (net (code "167") (name "Net-(U9-IO21_10)") (class "Default")
      (node (ref "R91") (pin "2") (pinfunction "2_2") (pintype "passive"))
      (node (ref "U9") (pin "C4") (pinfunction "IO21_10_C4") (pintype "bidirectional"))
    )
    (net (code "168") (name "Net-(U9-IO21_11)") (class "Default")
      (node (ref "R90") (pin "2") (pinfunction "2_2") (pintype "passive"))
      (node (ref "U9") (pin "A10") (pinfunction "IO21_13_A10") (pintype "bidirectional"))
      (node (ref "U9") (pin "C5") (pinfunction "IO21_11_C5") (pintype "bidirectional"))
      (node (ref "U9") (pin "C8") (pinfunction "IO21_12_C8") (pintype "bidirectional"))
    )
    (net (code "169") (name "Net-(U9-IO21_14)") (class "Default")
      (node (ref "R89") (pin "2") (pinfunction "2_2") (pintype "passive"))
      (node (ref "U9") (pin "B10") (pinfunction "IO21_14_B10") (pintype "bidirectional"))
    )
    (net (code "170") (name "Net-(U10-BCBUS3)") (class "Default")
      (node (ref "R106") (pin "1") (pinfunction "1_1") (pintype "passive"))
      (node (ref "U10") (pin "54") (pinfunction "BCBUS3_54") (pintype "bidirectional"))
    )
    (net (code "171") (name "Net-(U10-BCBUS4)") (class "Default")
      (node (ref "R107") (pin "1") (pinfunction "1_1") (pintype "passive"))
      (node (ref "U10") (pin "55") (pinfunction "BCBUS4_55") (pintype "bidirectional"))
    )
    (net (code "172") (name "Net-(U10-BDBUS0)") (class "Default")
      (node (ref "R103") (pin "1") (pinfunction "1_1") (pintype "passive"))
      (node (ref "U10") (pin "38") (pinfunction "BDBUS0_38") (pintype "bidirectional"))
    )
    (net (code "173") (name "Net-(U10-BDBUS1)") (class "Default")
      (node (ref "R104") (pin "1") (pinfunction "1_1") (pintype "passive"))
      (node (ref "U10") (pin "39") (pinfunction "BDBUS1_39") (pintype "bidirectional"))
    )
    (net (code "174") (name "Net-(U10-BDBUS2)") (class "Default")
      (node (ref "R105") (pin "2") (pinfunction "2_2") (pintype "passive"))
      (node (ref "U10") (pin "40") (pinfunction "BDBUS2_40") (pintype "bidirectional"))
    )
    (net (code "175") (name "Net-(U10-BDBUS3)") (class "Default")
      (node (ref "R105") (pin "1") (pinfunction "1_1") (pintype "passive"))
      (node (ref "U10") (pin "41") (pinfunction "BDBUS3_41") (pintype "bidirectional"))
    )
    (net (code "176") (name "Net-(U10-EECLK)") (class "Default")
      (node (ref "R112") (pin "1") (pinfunction "1_1") (pintype "passive"))
      (node (ref "U10") (pin "62") (pinfunction "EECLK_62") (pintype "bidirectional"))
      (node (ref "U11") (pin "2") (pinfunction "SK_2") (pintype "bidirectional"))
    )
    (net (code "177") (name "Net-(U10-EECS)") (class "Default")
      (node (ref "R111") (pin "1") (pinfunction "1_1") (pintype "passive"))
      (node (ref "U10") (pin "63") (pinfunction "EECS_63") (pintype "bidirectional"))
      (node (ref "U11") (pin "1") (pinfunction "CS_1") (pintype "bidirectional"))
    )
    (net (code "178") (name "Net-(U10-EEDATA)") (class "Default")
      (node (ref "R108") (pin "2") (pinfunction "2_2") (pintype "passive"))
      (node (ref "U10") (pin "61") (pinfunction "EEDATA_61") (pintype "bidirectional"))
      (node (ref "U11") (pin "3") (pinfunction "DIN_3") (pintype "bidirectional"))
    )
    (net (code "179") (name "Net-(U10-OSCI)") (class "Default")
      (node (ref "C72") (pin "1") (pinfunction "1_1") (pintype "passive"))
      (node (ref "U10") (pin "2") (pinfunction "OSCI_2") (pintype "bidirectional"))
      (node (ref "Y1") (pin "P$3") (pinfunction "P$3_P$3") (pintype "bidirectional"))
    )
    (net (code "180") (name "Net-(U10-OSCO)") (class "Default")
      (node (ref "C71") (pin "1") (pinfunction "1_1") (pintype "passive"))
      (node (ref "U10") (pin "3") (pinfunction "OSCO_3") (pintype "bidirectional"))
      (node (ref "Y1") (pin "P$1") (pinfunction "P$1_P$1") (pintype "bidirectional"))
    )
    (net (code "181") (name "Net-(U10-REF)") (class "Default")
      (node (ref "R110") (pin "2") (pinfunction "2_2") (pintype "passive"))
      (node (ref "U10") (pin "6") (pinfunction "REF_6") (pintype "bidirectional"))
    )
    (net (code "182") (name "Net-(U10-RESET)") (class "Default")
      (node (ref "R109") (pin "2") (pinfunction "2_2") (pintype "passive"))
      (node (ref "U10") (pin "14") (pinfunction "RESET_14") (pintype "bidirectional"))
    )
    (net (code "183") (name "Net-(U10-VPHY)") (class "Default")
      (node (ref "C59") (pin "1") (pinfunction "1_1") (pintype "passive"))
      (node (ref "C70") (pin "1") (pinfunction "1_1") (pintype "passive"))
      (node (ref "FB2") (pin "2") (pinfunction "2_2") (pintype "passive"))
      (node (ref "U10") (pin "4") (pinfunction "VPHY_4") (pintype "bidirectional"))
    )
    (net (code "184") (name "Net-(U10-VPLL)") (class "Default")
      (node (ref "C58") (pin "1") (pinfunction "1_1") (pintype "passive"))
      (node (ref "C69") (pin "1") (pinfunction "1_1") (pintype "passive"))
      (node (ref "FB1") (pin "2") (pinfunction "2_2") (pintype "passive"))
      (node (ref "U10") (pin "9") (pinfunction "VPLL_9") (pintype "bidirectional"))
    )
    (net (code "185") (name "Net-(U11-DOUT)") (class "Default")
      (node (ref "R108") (pin "1") (pinfunction "1_1") (pintype "passive"))
      (node (ref "R113") (pin "1") (pinfunction "1_1") (pintype "passive"))
      (node (ref "U11") (pin "4") (pinfunction "DOUT_4") (pintype "bidirectional"))
    )
    (net (code "186") (name "unconnected-(U$5-ID-Pad4)") (class "Default")
      (node (ref "U$5") (pin "4") (pinfunction "ID_4") (pintype "bidirectional"))
    )
    (net (code "187") (name "unconnected-(U2-NC-Pad20)") (class "Default")
      (node (ref "U2") (pin "20") (pinfunction "NC_20") (pintype "passive"))
    )
    (net (code "188") (name "unconnected-(U2-NC_2-Pad4)") (class "Default")
      (node (ref "U2") (pin "4") (pinfunction "NC_2_4") (pintype "passive"))
    )
    (net (code "189") (name "unconnected-(U2-NC_3-Pad17)") (class "Default")
      (node (ref "U2") (pin "17") (pinfunction "NC_3_17") (pintype "passive"))
    )
    (net (code "190") (name "unconnected-(U7-ADEVT-Pad58)") (class "Default")
      (node (ref "U7") (pin "58") (pinfunction "ADEVT_58") (pintype "bidirectional"))
    )
    (net (code "191") (name "unconnected-(U7-ECLK-Pad84)") (class "Default")
      (node (ref "U7") (pin "84") (pinfunction "ECLK_84") (pintype "bidirectional"))
    )
    (net (code "192") (name "unconnected-(U7-FLTP1-Pad3)") (class "Default")
      (node (ref "U7") (pin "3") (pinfunction "FLTP1_3") (pintype "bidirectional"))
    )
    (net (code "193") (name "unconnected-(U7-FLTP2-Pad4)") (class "Default")
      (node (ref "U7") (pin "4") (pinfunction "FLTP2_4") (pintype "bidirectional"))
    )
    (net (code "194") (name "unconnected-(U7-MIBSPI1CLK-Pad67)") (class "Default")
      (node (ref "U7") (pin "67") (pinfunction "MIBSPI1CLK_67") (pintype "bidirectional"))
    )
    (net (code "195") (name "unconnected-(U7-MIBSPI1NCS[0]-Pad73)") (class "Default")
      (node (ref "U7") (pin "73") (pinfunction "MIBSPI1NCS[0]_73") (pintype "bidirectional"))
    )
    (net (code "196") (name "unconnected-(U7-MIBSPI1NCS[1]-Pad93)") (class "Default")
      (node (ref "U7") (pin "93") (pinfunction "MIBSPI1NCS[1]_93") (pintype "bidirectional"))
    )
    (net (code "197") (name "unconnected-(U7-MIBSPI1NCS[2]-Pad27)") (class "Default")
      (node (ref "U7") (pin "27") (pinfunction "MIBSPI1NCS[2]_27") (pintype "bidirectional"))
    )
    (net (code "198") (name "unconnected-(U7-MIBSPI1NCS[3]-Pad39)") (class "Default")
      (node (ref "U7") (pin "39") (pinfunction "MIBSPI1NCS[3]_39") (pintype "bidirectional"))
    )
    (net (code "199") (name "unconnected-(U7-MIBSPI1NENA-Pad68)") (class "Default")
      (node (ref "U7") (pin "68") (pinfunction "MIBSPI1NENA_68") (pintype "bidirectional"))
    )
    (net (code "200") (name "unconnected-(U7-MIBSPI1SIMO-Pad65)") (class "Default")
      (node (ref "U7") (pin "65") (pinfunction "MIBSPI1SIMO_65") (pintype "bidirectional"))
    )
    (net (code "201") (name "unconnected-(U7-MIBSPI1SOMI-Pad66)") (class "Default")
      (node (ref "U7") (pin "66") (pinfunction "MIBSPI1SOMI_66") (pintype "bidirectional"))
    )
    (net (code "202") (name "unconnected-(U7-N2HET[0]-Pad19)") (class "Default")
      (node (ref "U7") (pin "19") (pinfunction "N2HET[0]_19") (pintype "bidirectional"))
    )
    (net (code "203") (name "unconnected-(U7-N2HET[2]-Pad22)") (class "Default")
      (node (ref "U7") (pin "22") (pinfunction "N2HET[2]_22") (pintype "bidirectional"))
    )
    (net (code "204") (name "unconnected-(U7-N2HET[4]-Pad25)") (class "Default")
      (node (ref "U7") (pin "25") (pinfunction "N2HET[4]_25") (pintype "bidirectional"))
    )
    (net (code "205") (name "unconnected-(U7-N2HET[6]-Pad26)") (class "Default")
      (node (ref "U7") (pin "26") (pinfunction "N2HET[6]_26") (pintype "bidirectional"))
    )
    (net (code "206") (name "unconnected-(U7-N2HET[8]-Pad74)") (class "Default")
      (node (ref "U7") (pin "74") (pinfunction "N2HET[8]_74") (pintype "bidirectional"))
    )
    (net (code "207") (name "unconnected-(U7-N2HET[10-Pad83)") (class "Default")
      (node (ref "U7") (pin "83") (pinfunction "N2HET[10_83") (pintype "bidirectional"))
    )
    (net (code "208") (name "unconnected-(U7-N2HET[12]-Pad89)") (class "Default")
      (node (ref "U7") (pin "89") (pinfunction "N2HET[12]_89") (pintype "bidirectional"))
    )
    (net (code "209") (name "unconnected-(U7-N2HET[14]-Pad90)") (class "Default")
      (node (ref "U7") (pin "90") (pinfunction "N2HET[14]_90") (pintype "bidirectional"))
    )
    (net (code "210") (name "unconnected-(U7-N2HET[16]-Pad97)") (class "Default")
      (node (ref "U7") (pin "97") (pinfunction "N2HET[16]_97") (pintype "bidirectional"))
    )
    (net (code "211") (name "unconnected-(U7-N2HET[18]-Pad98)") (class "Default")
      (node (ref "U7") (pin "98") (pinfunction "N2HET[18]_98") (pintype "bidirectional"))
    )
    (net (code "212") (name "unconnected-(U7-N2HET[022]-Pad11)") (class "Default")
      (node (ref "U7") (pin "11") (pinfunction "N2HET[022]_11") (pintype "bidirectional"))
    )
    (net (code "213") (name "unconnected-(U7-N2HET[024]-Pad64)") (class "Default")
      (node (ref "U7") (pin "64") (pinfunction "N2HET[024]_64") (pintype "bidirectional"))
    )
    (net (code "214") (name "unconnected-(U7-NERROR-Pad82)") (class "Default")
      (node (ref "U7") (pin "82") (pinfunction "NERROR_82") (pintype "bidirectional"))
    )
    (net (code "215") (name "unconnected-(U7-NPORRST-Pad31)") (class "Default")
      (node (ref "U7") (pin "31") (pinfunction "NPORRST_31") (pintype "bidirectional"))
    )
    (net (code "216") (name "unconnected-(U7-SPI2CLK-Pad71)") (class "Default")
      (node (ref "U7") (pin "71") (pinfunction "SPI2CLK_71") (pintype "bidirectional"))
    )
    (net (code "217") (name "unconnected-(U7-SPI2NCS[0]-Pad23)") (class "Default")
      (node (ref "U7") (pin "23") (pinfunction "SPI2NCS[0]_23") (pintype "bidirectional"))
    )
    (net (code "218") (name "unconnected-(U7-SPI2SIMO-Pad70)") (class "Default")
      (node (ref "U7") (pin "70") (pinfunction "SPI2SIMO_70") (pintype "bidirectional"))
    )
    (net (code "219") (name "unconnected-(U7-SPI2SOMI-Pad69)") (class "Default")
      (node (ref "U7") (pin "69") (pinfunction "SPI2SOMI_69") (pintype "bidirectional"))
    )
    (net (code "220") (name "unconnected-(U7-SPI3CLK-Pad36)") (class "Default")
      (node (ref "U7") (pin "36") (pinfunction "SPI3CLK_36") (pintype "bidirectional"))
    )
    (net (code "221") (name "unconnected-(U7-SPI3NCS[0]-Pad38)") (class "Default")
      (node (ref "U7") (pin "38") (pinfunction "SPI3NCS[0]_38") (pintype "bidirectional"))
    )
    (net (code "222") (name "unconnected-(U7-SPI3NENA-Pad37)") (class "Default")
      (node (ref "U7") (pin "37") (pinfunction "SPI3NENA_37") (pintype "bidirectional"))
    )
    (net (code "223") (name "unconnected-(U7-SPI3SIMO-Pad35)") (class "Default")
      (node (ref "U7") (pin "35") (pinfunction "SPI3SIMO_35") (pintype "bidirectional"))
    )
    (net (code "224") (name "unconnected-(U7-SPI3SOMI-Pad34)") (class "Default")
      (node (ref "U7") (pin "34") (pinfunction "SPI3SOMI_34") (pintype "bidirectional"))
    )
    (net (code "225") (name "unconnected-(U7-TEST-Pad24)") (class "Default")
      (node (ref "U7") (pin "24") (pinfunction "TEST_24") (pintype "bidirectional"))
    )
    (net (code "226") (name "unconnected-(U9-IO12_15-PadG10)") (class "Default")
      (node (ref "U9") (pin "G10") (pinfunction "IO12_15_G10") (pintype "bidirectional"))
    )
    (net (code "227") (name "unconnected-(U9-IO21_15-PadC10)") (class "Default")
      (node (ref "U9") (pin "C10") (pinfunction "IO21_15_C10") (pintype "bidirectional"))
    )
    (net (code "228") (name "unconnected-(U9-IO21_16-PadE8)") (class "Default")
      (node (ref "U9") (pin "E8") (pinfunction "IO21_16_E8") (pintype "bidirectional"))
    )
    (net (code "229") (name "unconnected-(U9-NC1-PadD8)") (class "Default")
      (node (ref "U9") (pin "D8") (pinfunction "NC1_D8") (pintype "bidirectional"))
    )
    (net (code "230") (name "unconnected-(U9-NC2-PadE10)") (class "Default")
      (node (ref "U9") (pin "E10") (pinfunction "NC2_E10") (pintype "bidirectional"))
    )
    (net (code "231") (name "unconnected-(U9-NC3-PadH7)") (class "Default")
      (node (ref "U9") (pin "H7") (pinfunction "NC3_H7") (pintype "bidirectional"))
    )
    (net (code "232") (name "unconnected-(U9-NC4-PadK4)") (class "Default")
      (node (ref "U9") (pin "K4") (pinfunction "NC4_K4") (pintype "bidirectional"))
    )
    (net (code "233") (name "unconnected-(U9-NC5-PadK6)") (class "Default")
      (node (ref "U9") (pin "K6") (pinfunction "NC5_K6") (pintype "bidirectional"))
    )
    (net (code "234") (name "unconnected-(U9-NC6-PadA4)") (class "Default")
      (node (ref "U9") (pin "A4") (pinfunction "NC6_A4") (pintype "bidirectional"))
    )
    (net (code "235") (name "unconnected-(U9-NC7-PadA5)") (class "Default")
      (node (ref "U9") (pin "A5") (pinfunction "NC7_A5") (pintype "bidirectional"))
    )
    (net (code "236") (name "unconnected-(U9-NC8-PadA7)") (class "Default")
      (node (ref "U9") (pin "A7") (pinfunction "NC8_A7") (pintype "bidirectional"))
    )
    (net (code "237") (name "unconnected-(U9-NC9-PadA8)") (class "Default")
      (node (ref "U9") (pin "A8") (pinfunction "NC9_A8") (pintype "bidirectional"))
    )
    (net (code "238") (name "unconnected-(U9-NC10-PadA9)") (class "Default")
      (node (ref "U9") (pin "A9") (pinfunction "NC10_A9") (pintype "bidirectional"))
    )
    (net (code "239") (name "unconnected-(U9-NC11-PadC3)") (class "Default")
      (node (ref "U9") (pin "C3") (pinfunction "NC11_C3") (pintype "bidirectional"))
    )
    (net (code "240") (name "unconnected-(U9-NC12-PadK7)") (class "Default")
      (node (ref "U9") (pin "K7") (pinfunction "NC12_K7") (pintype "bidirectional"))
    )
    (net (code "241") (name "unconnected-(U10-BCBUS0-Pad48)") (class "Default")
      (node (ref "U10") (pin "48") (pinfunction "BCBUS0_48") (pintype "bidirectional"))
    )
    (net (code "242") (name "unconnected-(U10-BCBUS7-Pad59)") (class "Default")
      (node (ref "U10") (pin "59") (pinfunction "BCBUS7_59") (pintype "bidirectional"))
    )
    (net (code "243") (name "unconnected-(U10-BDBUS4-Pad43)") (class "Default")
      (node (ref "U10") (pin "43") (pinfunction "BDBUS4_43") (pintype "bidirectional"))
    )
    (net (code "244") (name "unconnected-(U10-BDBUS5-Pad44)") (class "Default")
      (node (ref "U10") (pin "44") (pinfunction "BDBUS5_44") (pintype "bidirectional"))
    )
    (net (code "245") (name "unconnected-(U10-BDBUS6-Pad45)") (class "Default")
      (node (ref "U10") (pin "45") (pinfunction "BDBUS6_45") (pintype "bidirectional"))
    )
    (net (code "246") (name "unconnected-(U10-BDBUS7-Pad46)") (class "Default")
      (node (ref "U10") (pin "46") (pinfunction "BDBUS7_46") (pintype "bidirectional"))
    )
    (net (code "247") (name "unconnected-(U11-NC-Pad7)") (class "Default")
      (node (ref "U11") (pin "7") (pinfunction "NC_7") (pintype "bidirectional"))
    )
    (net (code "248") (name "unconnected-(X1AA-1-Pad33)") (class "Default")
      (node (ref "X1") (pin "33") (pinfunction "1_33") (pintype "passive"))
    )
    (net (code "249") (name "unconnected-(X1AB-1-Pad34)") (class "Default")
      (node (ref "X1") (pin "34") (pinfunction "1_34") (pintype "passive"))
    )
    (net (code "250") (name "unconnected-(X1AC-1-Pad35)") (class "Default")
      (node (ref "X1") (pin "35") (pinfunction "1_35") (pintype "passive"))
    )
    (net (code "251") (name "unconnected-(X1AD-1-Pad36)") (class "Default")
      (node (ref "X1") (pin "36") (pinfunction "1_36") (pintype "passive"))
    )
    (net (code "252") (name "unconnected-(X1AE-1-Pad37)") (class "Default")
      (node (ref "X1") (pin "37") (pinfunction "1_37") (pintype "passive"))
    )
    (net (code "253") (name "unconnected-(X1Y-1-Pad31)") (class "Default")
      (node (ref "X1") (pin "31") (pinfunction "1_31") (pintype "passive"))
    )
    (net (code "254") (name "unconnected-(X1Z-1-Pad32)") (class "Default")
      (node (ref "X1") (pin "32") (pinfunction "1_32") (pintype "passive"))
    )
  )
)
